# PicoUSBMotherboardV3_1.net
KiCad netlist of a schematic drawn in EasyEDA Pro
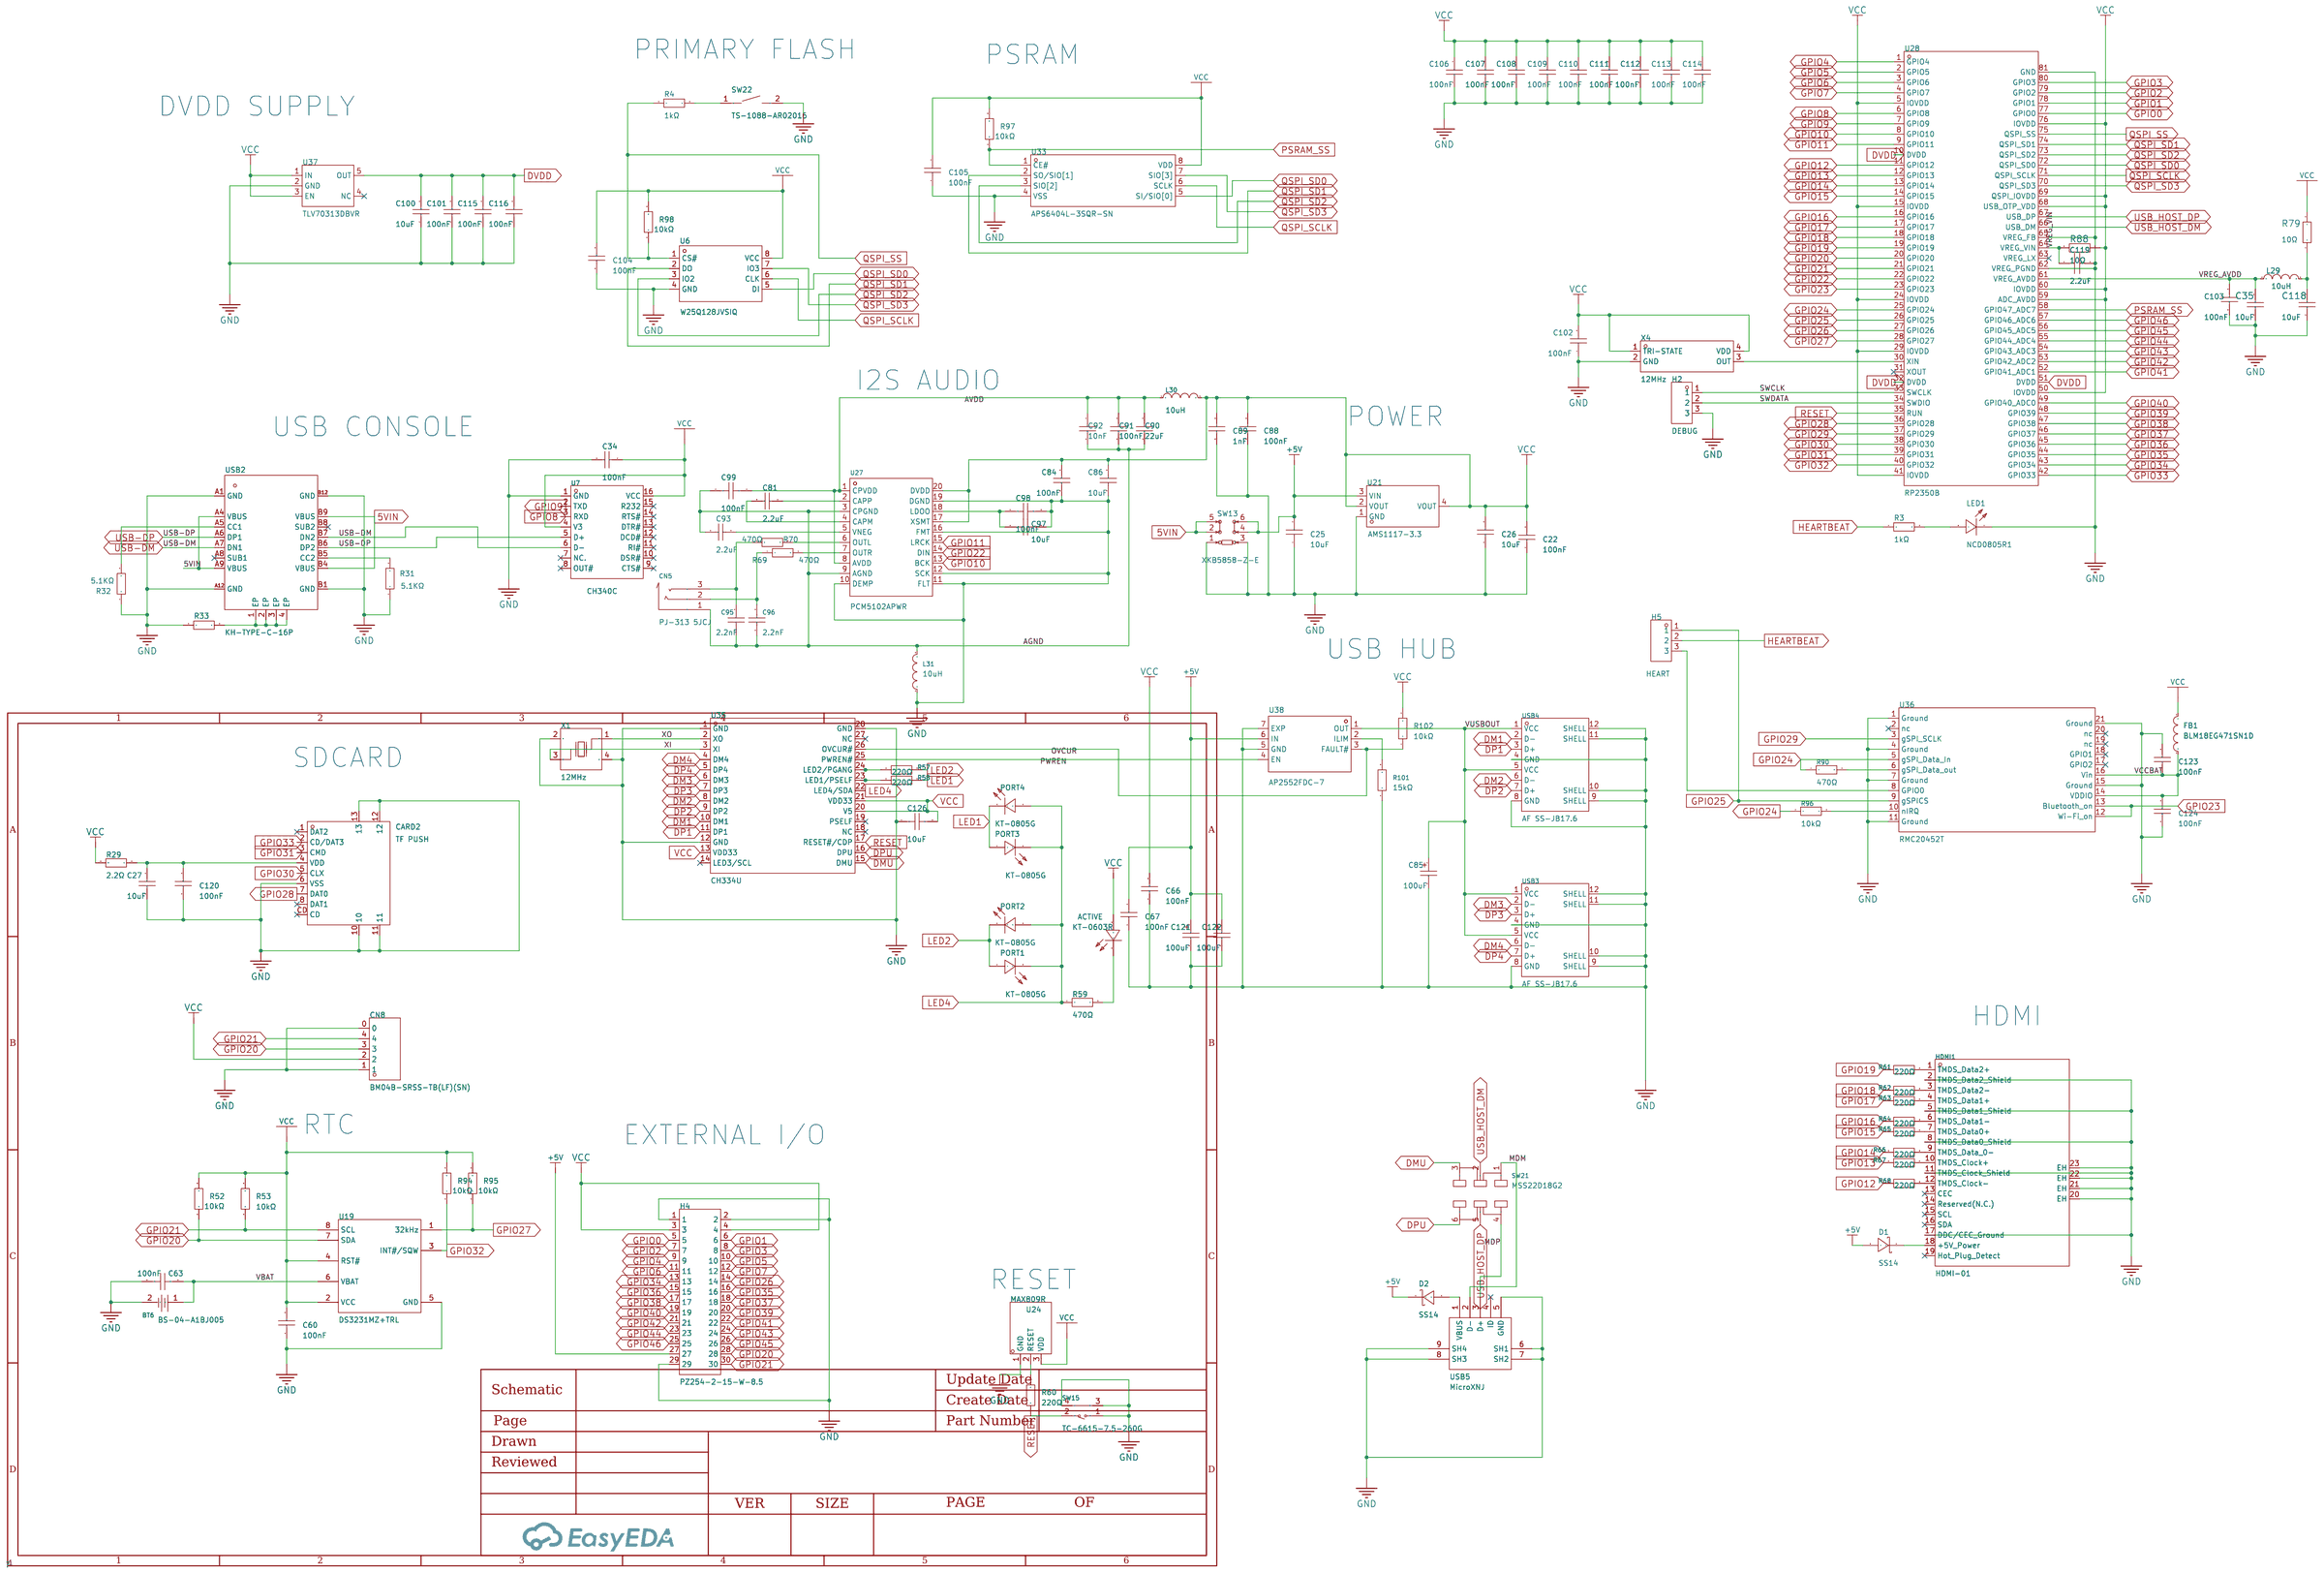
[diagram p0: schematic sheet]

(export (version "E")
  (design (tool "Eeschema 10.0.6"))
  (components
    (comp (ref "ACTIVE")
      (value "KT-0603R")
      (footprint "easyedapro:LED0603-RD")
      (fields (field (name "Manufacturer") "KENTO"))
      (libsource (lib "easyedapro") (part "KT-0603R"))
    )
    (comp (ref "BT6")
      (value "BS-04-A1BJ005")
      (footprint "easyedapro:BAT-TH_BS-04-A1BJ004")
      (fields (field (name "Manufacturer") "MYOUNG(美阳)"))
      (libsource (lib "easyedapro") (part "BS-04-A1BJ005"))
    )
    (comp (ref "C22")
      (value "100nF")
      (fields
        (field (name "Manufacturer Part") "CL05B104KO5NNNC")
        (field (name "Manufacturer") "SAMSUNG(三星)")
      )
      (libsource (lib "easyedapro") (part "cl10a225ko8nnnc"))
    )
    (comp (ref "C25")
      (value "10uF")
      (footprint "easyedapro:C1206")
      (fields
        (field (name "Manufacturer Part") "CL31A106KBHNNNE")
        (field (name "Manufacturer") "SAMSUNG(三星)")
      )
      (libsource (lib "easyedapro") (part "CL31A106KBHNNNE"))
    )
    (comp (ref "C26")
      (value "10uF")
      (footprint "easyedapro:C1206")
      (fields
        (field (name "Manufacturer Part") "CL31A106KBHNNNE")
        (field (name "Manufacturer") "SAMSUNG(三星)")
      )
      (libsource (lib "easyedapro") (part "CL31A106KBHNNNE"))
    )
    (comp (ref "C27")
      (value "10uF")
      (footprint "easyedapro:C1206")
      (fields
        (field (name "Manufacturer Part") "CL31A106KBHNNNE")
        (field (name "Manufacturer") "SAMSUNG(三星)")
      )
      (libsource (lib "easyedapro") (part "CL31A106KBHNNNE"))
    )
    (comp (ref "C34")
      (value "100nF")
      (fields
        (field (name "Manufacturer Part") "CL05B104KO5NNNC")
        (field (name "Manufacturer") "SAMSUNG(三星)")
      )
      (libsource (lib "easyedapro") (part "cl10a225ko8nnnc"))
    )
    (comp (ref "C35")
      (value "10uF")
      (footprint "easyedapro:C1206")
      (fields
        (field (name "Manufacturer Part") "CL31A106KBHNNNE")
        (field (name "Manufacturer") "SAMSUNG(三星)")
      )
      (libsource (lib "easyedapro") (part "CL31A106KBHNNNE"))
    )
    (comp (ref "C60")
      (value "100nF")
      (footprint "easyedapro:C0603")
      (fields
        (field (name "Manufacturer Part") "CL05B104KO5NNNC")
        (field (name "Manufacturer") "SAMSUNG(三星)")
      )
      (libsource (lib "easyedapro") (part "CL10A225KO8NNNC"))
    )
    (comp (ref "C63")
      (value "100nF")
      (footprint "easyedapro:C0402")
      (fields
        (field (name "Manufacturer Part") "CL05B104KB54PNC")
        (field (name "Manufacturer") "SAMSUNG(三星)")
      )
      (libsource (lib "easyedapro") (part "CL05B104KB54PNC"))
    )
    (comp (ref "C66")
      (value "100nF")
      (fields
        (field (name "Manufacturer Part") "CL05B104KO5NNNC")
        (field (name "Manufacturer") "SAMSUNG(三星)")
      )
      (libsource (lib "easyedapro") (part "cl10a225ko8nnnc"))
    )
    (comp (ref "C67")
      (value "100nF")
      (fields
        (field (name "Manufacturer Part") "CL05B104KO5NNNC")
        (field (name "Manufacturer") "SAMSUNG(三星)")
      )
      (libsource (lib "easyedapro") (part "cl10a225ko8nnnc"))
    )
    (comp (ref "C81")
      (value "2.2uF")
      (footprint "easyedapro:C0603")
      (fields
        (field (name "Manufacturer Part") "CL10A225KO8NNNC")
        (field (name "Manufacturer") "SAMSUNG(三星)")
      )
      (libsource (lib "easyedapro") (part "CL10A225KO8NNNC"))
    )
    (comp (ref "C84")
      (value "100nF")
      (fields
        (field (name "Manufacturer Part") "CL05B104KO5NNNC")
        (field (name "Manufacturer") "SAMSUNG(三星)")
      )
      (libsource (lib "easyedapro") (part "cl10a225ko8nnnc"))
    )
    (comp (ref "C85")
      (value "100uF")
      (footprint "easyedapro:CASE-B_3528")
      (fields (field (name "Manufacturer Part") "TAJB107K006RNJ") (field (name "Manufacturer") "Kyocera AVX"))
      (libsource (lib "easyedapro") (part "TAJB107K006RNJ"))
    )
    (comp (ref "C86")
      (value "10uF")
      (footprint "easyedapro:C1206")
      (fields
        (field (name "Manufacturer Part") "CL31A106KBHNNNE")
        (field (name "Manufacturer") "SAMSUNG(三星)")
      )
      (libsource (lib "easyedapro") (part "CL31A106KBHNNNE"))
    )
    (comp (ref "C88")
      (value "100nF")
      (fields
        (field (name "Manufacturer Part") "CL05B104KO5NNNC")
        (field (name "Manufacturer") "SAMSUNG(三星)")
      )
      (libsource (lib "easyedapro") (part "cl10a225ko8nnnc"))
    )
    (comp (ref "C89")
      (value "1nF")
      (footprint "easyedapro:C0805")
      (fields
        (field (name "Manufacturer Part") "CL21B102KBCNNNC")
        (field (name "Manufacturer") "SAMSUNG(三星)")
      )
      (libsource (lib "easyedapro") (part "CL21B102KBCNNNC"))
    )
    (comp (ref "C90")
      (value "22uF")
      (footprint "easyedapro:C1206")
      (fields
        (field (name "Manufacturer Part") "CL31A226KAHNNNE")
        (field (name "Manufacturer") "SAMSUNG(三星)")
      )
      (libsource (lib "easyedapro") (part "CL31A226KAHNNNE"))
    )
    (comp (ref "C91")
      (value "100nF")
      (fields
        (field (name "Manufacturer Part") "CL05B104KO5NNNC")
        (field (name "Manufacturer") "SAMSUNG(三星)")
      )
      (libsource (lib "easyedapro") (part "cl10a225ko8nnnc"))
    )
    (comp (ref "C92")
      (value "10nF")
      (footprint "easyedapro:C0805")
      (fields
        (field (name "Manufacturer Part") "CL21B103KBANNNC")
        (field (name "Manufacturer") "SAMSUNG(三星)")
      )
      (libsource (lib "easyedapro") (part "CL21B103KBANNNC"))
    )
    (comp (ref "C93")
      (value "2.2uF")
      (footprint "easyedapro:C0603")
      (fields
        (field (name "Manufacturer Part") "CL10A225KO8NNNC")
        (field (name "Manufacturer") "SAMSUNG(三星)")
      )
      (libsource (lib "easyedapro") (part "CL10A225KO8NNNC"))
    )
    (comp (ref "C95")
      (value "2.2nF")
      (footprint "easyedapro:C0805")
      (fields
        (field (name "Manufacturer Part") "CL21C222JBFNNNE")
        (field (name "Manufacturer") "SAMSUNG(三星)")
      )
      (libsource (lib "easyedapro") (part "CL21C222JBFNNNE"))
    )
    (comp (ref "C96")
      (value "2.2nF")
      (footprint "easyedapro:C0805")
      (fields
        (field (name "Manufacturer Part") "CL21C222JBFNNNE")
        (field (name "Manufacturer") "SAMSUNG(三星)")
      )
      (libsource (lib "easyedapro") (part "CL21C222JBFNNNE"))
    )
    (comp (ref "C97")
      (value "10uF")
      (footprint "easyedapro:C0805")
      (fields
        (field (name "Manufacturer Part") "CL21A106KAYNNNE")
        (field (name "Manufacturer") "SAMSUNG(三星)")
      )
      (libsource (lib "easyedapro") (part "CL21A106KAYNNNE"))
    )
    (comp (ref "C98")
      (value "100nF")
      (footprint "easyedapro:C0805")
      (fields
        (field (name "Manufacturer Part") "CC0805KRX7R9BB104")
        (field (name "Manufacturer") "YAGEO(国巨)")
      )
      (libsource (lib "easyedapro") (part "CC0805KRX7R9BB104"))
    )
    (comp (ref "C99")
      (value "100nF")
      (footprint "easyedapro:C0805")
      (fields
        (field (name "Manufacturer Part") "CC0805KRX7R9BB104")
        (field (name "Manufacturer") "YAGEO(国巨)")
      )
      (libsource (lib "easyedapro") (part "CC0805KRX7R9BB104"))
    )
    (comp (ref "C100")
      (value "10uF")
      (footprint "easyedapro:C1206")
      (fields
        (field (name "Manufacturer Part") "CL31A106KBHNNNE")
        (field (name "Manufacturer") "SAMSUNG(三星)")
      )
      (libsource (lib "easyedapro") (part "CL31A106KBHNNNE"))
    )
    (comp (ref "C101")
      (value "100nF")
      (fields
        (field (name "Manufacturer Part") "CL05B104KO5NNNC")
        (field (name "Manufacturer") "SAMSUNG(三星)")
      )
      (libsource (lib "easyedapro") (part "cl10a225ko8nnnc"))
    )
    (comp (ref "C102")
      (value "100nF")
      (fields
        (field (name "Manufacturer Part") "CL05B104KO5NNNC")
        (field (name "Manufacturer") "SAMSUNG(三星)")
      )
      (libsource (lib "easyedapro") (part "cl10a225ko8nnnc"))
    )
    (comp (ref "C103")
      (value "100nF")
      (fields
        (field (name "Manufacturer Part") "CL05B104KO5NNNC")
        (field (name "Manufacturer") "SAMSUNG(三星)")
      )
      (libsource (lib "easyedapro") (part "cl10a225ko8nnnc"))
    )
    (comp (ref "C104")
      (value "100nF")
      (footprint "easyedapro:C0805")
      (fields
        (field (name "Manufacturer Part") "CL21B104KCFNNNE")
        (field (name "Manufacturer") "SAMSUNG(三星)")
      )
      (libsource (lib "easyedapro") (part "CL21B104KCFNNNE"))
    )
    (comp (ref "C105")
      (value "100nF")
      (fields
        (field (name "Manufacturer Part") "CL05B104KO5NNNC")
        (field (name "Manufacturer") "SAMSUNG(三星)")
      )
      (libsource (lib "easyedapro") (part "cl10a225ko8nnnc"))
    )
    (comp (ref "C106")
      (value "100nF")
      (fields
        (field (name "Manufacturer Part") "CL05B104KO5NNNC")
        (field (name "Manufacturer") "SAMSUNG(三星)")
      )
      (libsource (lib "easyedapro") (part "cl10a225ko8nnnc"))
    )
    (comp (ref "C107")
      (value "100nF")
      (fields
        (field (name "Manufacturer Part") "CL05B104KO5NNNC")
        (field (name "Manufacturer") "SAMSUNG(三星)")
      )
      (libsource (lib "easyedapro") (part "cl10a225ko8nnnc"))
    )
    (comp (ref "C108")
      (value "100nF")
      (fields
        (field (name "Manufacturer Part") "CL05B104KO5NNNC")
        (field (name "Manufacturer") "SAMSUNG(三星)")
      )
      (libsource (lib "easyedapro") (part "cl10a225ko8nnnc"))
    )
    (comp (ref "C109")
      (value "100nF")
      (fields
        (field (name "Manufacturer Part") "CL05B104KO5NNNC")
        (field (name "Manufacturer") "SAMSUNG(三星)")
      )
      (libsource (lib "easyedapro") (part "cl10a225ko8nnnc"))
    )
    (comp (ref "C110")
      (value "100nF")
      (fields
        (field (name "Manufacturer Part") "CL05B104KO5NNNC")
        (field (name "Manufacturer") "SAMSUNG(三星)")
      )
      (libsource (lib "easyedapro") (part "cl10a225ko8nnnc"))
    )
    (comp (ref "C111")
      (value "100nF")
      (fields
        (field (name "Manufacturer Part") "CL05B104KO5NNNC")
        (field (name "Manufacturer") "SAMSUNG(三星)")
      )
      (libsource (lib "easyedapro") (part "cl10a225ko8nnnc"))
    )
    (comp (ref "C112")
      (value "100nF")
      (fields
        (field (name "Manufacturer Part") "CL05B104KO5NNNC")
        (field (name "Manufacturer") "SAMSUNG(三星)")
      )
      (libsource (lib "easyedapro") (part "cl10a225ko8nnnc"))
    )
    (comp (ref "C113")
      (value "100nF")
      (fields
        (field (name "Manufacturer Part") "CL05B104KO5NNNC")
        (field (name "Manufacturer") "SAMSUNG(三星)")
      )
      (libsource (lib "easyedapro") (part "cl10a225ko8nnnc"))
    )
    (comp (ref "C114")
      (value "100nF")
      (fields
        (field (name "Manufacturer Part") "CL05B104KO5NNNC")
        (field (name "Manufacturer") "SAMSUNG(三星)")
      )
      (libsource (lib "easyedapro") (part "cl10a225ko8nnnc"))
    )
    (comp (ref "C115")
      (value "100nF")
      (fields
        (field (name "Manufacturer Part") "CL05B104KO5NNNC")
        (field (name "Manufacturer") "SAMSUNG(三星)")
      )
      (libsource (lib "easyedapro") (part "cl10a225ko8nnnc"))
    )
    (comp (ref "C116")
      (value "100nF")
      (fields
        (field (name "Manufacturer Part") "CL05B104KO5NNNC")
        (field (name "Manufacturer") "SAMSUNG(三星)")
      )
      (libsource (lib "easyedapro") (part "cl10a225ko8nnnc"))
    )
    (comp (ref "C118")
      (value "10uF")
      (footprint "easyedapro:C1206")
      (fields
        (field (name "Manufacturer Part") "CL31A106KBHNNNE")
        (field (name "Manufacturer") "SAMSUNG(三星)")
      )
      (libsource (lib "easyedapro") (part "CL31A106KBHNNNE"))
    )
    (comp (ref "C119")
      (value "2.2uF")
      (footprint "easyedapro:C0402")
      (fields
        (field (name "Manufacturer Part") "CL05A225MQ5NSNC")
        (field (name "Manufacturer") "SAMSUNG(三星)")
      )
      (libsource (lib "easyedapro") (part "CL05A225MQ5NSNC"))
    )
    (comp (ref "C120")
      (value "100nF")
      (footprint "easyedapro:C0805")
      (fields
        (field (name "Manufacturer Part") "CL21B104KCFNNNE")
        (field (name "Manufacturer") "SAMSUNG(三星)")
      )
      (libsource (lib "easyedapro") (part "CL21B104KCFNNNE"))
    )
    (comp (ref "C121")
      (value "100uF")
      (footprint "easyedapro:CASE-B_3528")
      (fields (field (name "Manufacturer Part") "TAJB107K006RNJ") (field (name "Manufacturer") "Kyocera AVX"))
      (libsource (lib "easyedapro") (part "TAJB107K006RNJ"))
    )
    (comp (ref "C122")
      (value "100uF")
      (footprint "easyedapro:CASE-B_3528")
      (fields (field (name "Manufacturer Part") "TAJB107K006RNJ") (field (name "Manufacturer") "Kyocera AVX"))
      (libsource (lib "easyedapro") (part "TAJB107K006RNJ"))
    )
    (comp (ref "C123")
      (value "100nF")
      (fields
        (field (name "Manufacturer Part") "CL05B104KO5NNNC")
        (field (name "Manufacturer") "SAMSUNG(三星)")
      )
      (libsource (lib "easyedapro") (part "cl10a225ko8nnnc"))
    )
    (comp (ref "C124")
      (value "100nF")
      (fields
        (field (name "Manufacturer Part") "CL05B104KO5NNNC")
        (field (name "Manufacturer") "SAMSUNG(三星)")
      )
      (libsource (lib "easyedapro") (part "cl10a225ko8nnnc"))
    )
    (comp (ref "C126")
      (value "10uF")
      (footprint "easyedapro:C0603")
      (description "Capacitance:10uF Tolerance:±10% Tolerance:±10% Voltage Rating:10V Temperature Coefficient:X5R")
      (fields
        (field (name "Manufacturer Part") "CL10A106KP8NNNC")
        (field (name "Manufacturer") "SAMSUNG(三星)")
      )
      (libsource (lib "easyedapro") (part "CL10A106KP8NNNC"))
    )
    (comp (ref "CARD2")
      (value "TF PUSH")
      (footprint "easyedapro:TF-SMD_TF-PUSH")
      (fields (field (name "Manufacturer") "SHOU HAN(首韩)"))
      (libsource (lib "easyedapro") (part "TF PUSH"))
    )
    (comp (ref "CN5")
      (value "PJ-313 5JCJ")
      (footprint "easyedapro:AUDIO-TH_PJ-313_5JCJ")
      (fields (field (name "Manufacturer") "SHOU HAN(首韩)"))
      (libsource (lib "easyedapro") (part "PJ-313 5JCJ"))
    )
    (comp (ref "CN8")
      (value "BM04B-SRSS-TB(LF)(SN)")
      (footprint "easyedapro:CONN-SMD_BM04B-SRSS-TB")
      (fields (field (name "Manufacturer") "JST"))
      (libsource (lib "easyedapro") (part "BM04B-SRSS-TB(LF)(SN)"))
    )
    (comp (ref "D1")
      (value "SS14")
      (footprint "easyedapro:SMA_L4.2-W2.6-LS5.3-RD")
      (fields (field (name "Manufacturer") "MDD(辰达半导体)"))
      (libsource (lib "easyedapro") (part "SS14"))
    )
    (comp (ref "D2")
      (value "SS14")
      (footprint "easyedapro:SMA_L4.2-W2.6-LS5.3-RD")
      (fields (field (name "Manufacturer") "MDD(辰达半导体)"))
      (libsource (lib "easyedapro") (part "SS14"))
    )
    (comp (ref "FB1")
      (value "BLM18EG471SN1D")
      (footprint "easyedapro:L0603")
      (fields (field (name "Manufacturer") "muRata(村田)"))
      (libsource (lib "easyedapro") (part "BLM18EG471SN1D"))
    )
    (comp (ref "H2")
      (value "DEBUG")
      (footprint "easyedapro:HDR-TH_3P-P2.54-V-M")
      (fields (field (name "Manufacturer Part") "PZ254V-11-03P") (field (name "Manufacturer") "XFCN(兴飞)"))
      (libsource (lib "easyedapro") (part "PZ254V-11-03P_C2937625"))
    )
    (comp (ref "H4")
      (value "PZ254-2-15-W-8.5")
      (footprint "easyedapro:HDR-TH_30P-P2.54-H-M-R2-C15-S2.54-N")
      (fields (field (name "Manufacturer") "HCTL(华灿天禄)"))
      (libsource (lib "easyedapro") (part "PZ254-2-15-W-8.5"))
    )
    (comp (ref "H5")
      (value "HEART")
      (footprint "easyedapro:HDR-TH_3P-P2.54-V-M")
      (fields (field (name "Manufacturer Part") "PZ254V-11-03P") (field (name "Manufacturer") "XFCN(兴飞)"))
      (libsource (lib "easyedapro") (part "PZ254V-11-03P_C2937625"))
    )
    (comp (ref "HDMI1")
      (value "HDMI-01")
      (footprint "easyedapro:USB-SMD_HDMI-01")
      (fields (field (name "Manufacturer") "HCTL(华灿天禄)"))
      (libsource (lib "easyedapro") (part "HDMI-01"))
    )
    (comp (ref "L29")
      (value "10uH")
      (fields
        (field (name "Manufacturer Part") "SDFL2012S100KTF")
        (field (name "Manufacturer") "Sunlord(顺络)")
      )
      (libsource (lib "easyedapro") (part "SDFL2012S100KTF"))
    )
    (comp (ref "L30")
      (value "10uH")
      (footprint "easyedapro:L0805")
      (fields (field (name "Manufacturer Part") "MLZ2012M100HT000") (field (name "Manufacturer") "TDK"))
      (libsource (lib "easyedapro") (part "MLZ2012M100HT000"))
    )
    (comp (ref "L31")
      (value "10uH")
      (footprint "easyedapro:L0805")
      (fields (field (name "Manufacturer Part") "MLZ2012M100HT000") (field (name "Manufacturer") "TDK"))
      (libsource (lib "easyedapro") (part "MLZ2012M100HT000"))
    )
    (comp (ref "LED1")
      (value "NCD0805R1")
      (footprint "easyedapro:LED0805-RD")
      (description "Emitted Color:红灯")
      (fields (field (name "Manufacturer") "国星光电"))
      (libsource (lib "easyedapro") (part "FC-2012HRK-620D"))
    )
    (comp (ref "PORT1")
      (value "KT-0805G")
      (footprint "easyedapro:LED0805-R-RD")
      (fields (field (name "Manufacturer") "KENTO"))
      (libsource (lib "easyedapro") (part "0805G (Green)"))
    )
    (comp (ref "PORT2")
      (value "KT-0805G")
      (footprint "easyedapro:LED0805-R-RD")
      (fields (field (name "Manufacturer") "KENTO"))
      (libsource (lib "easyedapro") (part "0805G (Green)"))
    )
    (comp (ref "PORT3")
      (value "KT-0805G")
      (footprint "easyedapro:LED0805-R-RD")
      (fields (field (name "Manufacturer") "KENTO"))
      (libsource (lib "easyedapro") (part "0805G (Green)"))
    )
    (comp (ref "PORT4")
      (value "KT-0805G")
      (footprint "easyedapro:LED0805-R-RD")
      (fields (field (name "Manufacturer") "KENTO"))
      (libsource (lib "easyedapro") (part "0805G (Green)"))
    )
    (comp (ref "R3")
      (value "1kΩ")
      (footprint "easyedapro:R0603")
      (fields
        (field (name "Manufacturer Part") "0603WAF1001T5E")
        (field (name "Manufacturer") "UNI-ROYAL(厚声)")
      )
      (libsource (lib "easyedapro") (part "0603WAF1001T5E"))
    )
    (comp (ref "R4")
      (value "1kΩ")
      (footprint "easyedapro:R0603")
      (fields
        (field (name "Manufacturer Part") "0603WAF1001T5E")
        (field (name "Manufacturer") "UNI-ROYAL(厚声)")
      )
      (libsource (lib "easyedapro") (part "0603WAF1001T5E"))
    )
    (comp (ref "R29")
      (value "2.2Ω")
      (footprint "easyedapro:R0805")
      (fields (field (name "Manufacturer") "UNI-ROYAL(厚声)"))
      (libsource (lib "easyedapro") (part "0805W8F220KT5E"))
    )
    (comp (ref "R31")
      (value "5.1kΩ")
      (fields
        (field (name "Manufacturer Part") "5.1KΩ")
        (field (name "Manufacturer") "UNI-ROYAL(厚声)")
        (field (name "Tolerance") "±1%")
      )
      (libsource (lib "easyedapro") (part "0603waf5101t5e"))
    )
    (comp (ref "R32")
      (value "5.1kΩ")
      (fields
        (field (name "Manufacturer Part") "5.1KΩ")
        (field (name "Manufacturer") "UNI-ROYAL(厚声)")
        (field (name "Tolerance") "±1%")
      )
      (libsource (lib "easyedapro") (part "0603waf5101t5e"))
    )
    (comp (ref "R33")
      (value "1MΩ")
      (fields
        (field (name "Manufacturer Part") "0402WGF1004TCE")
        (field (name "Manufacturer") "UNI-ROYAL(厚声)")
      )
      (libsource (lib "easyedapro") (part "0603waf1004t5e"))
    )
    (comp (ref "R52")
      (value "10kΩ")
      (footprint "easyedapro:R0805")
      (fields
        (field (name "Manufacturer Part") "0805W8F1002T5E")
        (field (name "Manufacturer") "UNI-ROYAL(厚声)")
      )
      (libsource (lib "easyedapro") (part "0805W8F1002T5E"))
    )
    (comp (ref "R53")
      (value "10kΩ")
      (footprint "easyedapro:R0805")
      (fields
        (field (name "Manufacturer Part") "0805W8F1002T5E")
        (field (name "Manufacturer") "UNI-ROYAL(厚声)")
      )
      (libsource (lib "easyedapro") (part "0805W8F1002T5E"))
    )
    (comp (ref "R57")
      (value "220Ω")
      (footprint "easyedapro:R0805")
      (fields
        (field (name "Manufacturer Part") "0805W8F2200T5E")
        (field (name "Manufacturer") "UNI-ROYAL(厚声)")
      )
      (libsource (lib "easyedapro") (part "0805W8F2200T5E"))
    )
    (comp (ref "R58")
      (value "220Ω")
      (footprint "easyedapro:R0805")
      (fields
        (field (name "Manufacturer Part") "0805W8F2200T5E")
        (field (name "Manufacturer") "UNI-ROYAL(厚声)")
      )
      (libsource (lib "easyedapro") (part "0805W8F2200T5E"))
    )
    (comp (ref "R59")
      (value "470Ω")
      (footprint "easyedapro:R0603")
      (fields
        (field (name "Manufacturer Part") "0603WAF4700T5E")
        (field (name "Manufacturer") "UNI-ROYAL(厚声)")
      )
      (libsource (lib "easyedapro") (part "0603WAF4700T5E"))
    )
    (comp (ref "R60")
      (value "220Ω")
      (footprint "easyedapro:R0603")
      (fields
        (field (name "Manufacturer Part") "0603WAF2200T5E")
        (field (name "Manufacturer") "UNI-ROYAL(厚声)")
      )
      (libsource (lib "easyedapro") (part "0603WAF2200T5E"))
    )
    (comp (ref "R61")
      (value "220Ω")
      (footprint "easyedapro:R0603")
      (fields
        (field (name "Manufacturer Part") "0603WAF2200T5E")
        (field (name "Manufacturer") "UNI-ROYAL(厚声)")
      )
      (libsource (lib "easyedapro") (part "0603WAF2200T5E"))
    )
    (comp (ref "R62")
      (value "220Ω")
      (footprint "easyedapro:R0603")
      (fields
        (field (name "Manufacturer Part") "0603WAF2200T5E")
        (field (name "Manufacturer") "UNI-ROYAL(厚声)")
      )
      (libsource (lib "easyedapro") (part "0603WAF2200T5E"))
    )
    (comp (ref "R63")
      (value "220Ω")
      (footprint "easyedapro:R0603")
      (fields
        (field (name "Manufacturer Part") "0603WAF2200T5E")
        (field (name "Manufacturer") "UNI-ROYAL(厚声)")
      )
      (libsource (lib "easyedapro") (part "0603WAF2200T5E"))
    )
    (comp (ref "R64")
      (value "220Ω")
      (footprint "easyedapro:R0603")
      (fields
        (field (name "Manufacturer Part") "0603WAF2200T5E")
        (field (name "Manufacturer") "UNI-ROYAL(厚声)")
      )
      (libsource (lib "easyedapro") (part "0603WAF2200T5E"))
    )
    (comp (ref "R65")
      (value "220Ω")
      (footprint "easyedapro:R0603")
      (fields
        (field (name "Manufacturer Part") "0603WAF2200T5E")
        (field (name "Manufacturer") "UNI-ROYAL(厚声)")
      )
      (libsource (lib "easyedapro") (part "0603WAF2200T5E"))
    )
    (comp (ref "R66")
      (value "220Ω")
      (footprint "easyedapro:R0603")
      (fields
        (field (name "Manufacturer Part") "0603WAF2200T5E")
        (field (name "Manufacturer") "UNI-ROYAL(厚声)")
      )
      (libsource (lib "easyedapro") (part "0603WAF2200T5E"))
    )
    (comp (ref "R67")
      (value "220Ω")
      (footprint "easyedapro:R0603")
      (fields
        (field (name "Manufacturer Part") "0603WAF2200T5E")
        (field (name "Manufacturer") "UNI-ROYAL(厚声)")
      )
      (libsource (lib "easyedapro") (part "0603WAF2200T5E"))
    )
    (comp (ref "R68")
      (value "220Ω")
      (footprint "easyedapro:R0603")
      (fields
        (field (name "Manufacturer Part") "0603WAF2200T5E")
        (field (name "Manufacturer") "UNI-ROYAL(厚声)")
      )
      (libsource (lib "easyedapro") (part "0603WAF2200T5E"))
    )
    (comp (ref "R69")
      (value "470Ω")
      (footprint "easyedapro:R0603")
      (fields
        (field (name "Manufacturer Part") "0603WAF4700T5E")
        (field (name "Manufacturer") "UNI-ROYAL(厚声)")
      )
      (libsource (lib "easyedapro") (part "0603WAF4700T5E"))
    )
    (comp (ref "R70")
      (value "470Ω")
      (footprint "easyedapro:R0603")
      (fields
        (field (name "Manufacturer Part") "0603WAF4700T5E")
        (field (name "Manufacturer") "UNI-ROYAL(厚声)")
      )
      (libsource (lib "easyedapro") (part "0603WAF4700T5E"))
    )
    (comp (ref "R79")
      (value "10Ω")
      (footprint "easyedapro:R0805_NEW")
      (fields
        (field (name "Manufacturer Part") "0805W8F100JT5E")
        (field (name "Manufacturer") "UNI-ROYAL(厚声)")
      )
      (libsource (lib "easyedapro") (part "0805W8F100JT5E"))
    )
    (comp (ref "R88")
      (value "10Ω")
      (footprint "easyedapro:R0805_NEW")
      (fields
        (field (name "Manufacturer Part") "0805W8F100JT5E")
        (field (name "Manufacturer") "UNI-ROYAL(厚声)")
      )
      (libsource (lib "easyedapro") (part "0805W8F100JT5E"))
    )
    (comp (ref "R90")
      (value "470Ω")
      (footprint "easyedapro:R0402")
      (fields
        (field (name "Manufacturer Part") "0402WGF4700TCE")
        (field (name "Manufacturer") "UNI-ROYAL(厚声)")
      )
      (libsource (lib "easyedapro") (part "0402WGF4700TCE"))
    )
    (comp (ref "R94")
      (value "10kΩ")
      (footprint "easyedapro:R0805")
      (fields
        (field (name "Manufacturer Part") "0805W8F1002T5E")
        (field (name "Manufacturer") "UNI-ROYAL(厚声)")
      )
      (libsource (lib "easyedapro") (part "0805W8F1002T5E"))
    )
    (comp (ref "R95")
      (value "10kΩ")
      (footprint "easyedapro:R0805")
      (fields
        (field (name "Manufacturer Part") "0805W8F1002T5E")
        (field (name "Manufacturer") "UNI-ROYAL(厚声)")
      )
      (libsource (lib "easyedapro") (part "0805W8F1002T5E"))
    )
    (comp (ref "R96")
      (value "10kΩ")
      (footprint "easyedapro:R0603")
      (fields
        (field (name "Manufacturer Part") "0603WAF1002T5E")
        (field (name "Manufacturer") "UNI-ROYAL(厚声)")
      )
      (libsource (lib "easyedapro") (part "0603WAF1002T5E"))
    )
    (comp (ref "R97")
      (value "10kΩ")
      (footprint "easyedapro:R0805")
      (fields
        (field (name "Manufacturer Part") "0805W8F1002T5E")
        (field (name "Manufacturer") "UNI-ROYAL(厚声)")
      )
      (libsource (lib "easyedapro") (part "0805W8F1002T5E"))
    )
    (comp (ref "R98")
      (value "10kΩ")
      (footprint "easyedapro:R0805")
      (fields
        (field (name "Manufacturer Part") "0805W8F1002T5E")
        (field (name "Manufacturer") "UNI-ROYAL(厚声)")
      )
      (libsource (lib "easyedapro") (part "0805W8F1002T5E"))
    )
    (comp (ref "R101")
      (value "15kΩ")
      (footprint "easyedapro:R0402")
      (fields
        (field (name "Manufacturer Part") "0402WGF1502TCE")
        (field (name "Manufacturer") "UNI-ROYAL(厚声)")
      )
      (libsource (lib "easyedapro") (part "0402WGF1502TCE"))
    )
    (comp (ref "R102")
      (value "10kΩ")
      (footprint "easyedapro:R0805")
      (fields
        (field (name "Manufacturer Part") "0805W8F1002T5E")
        (field (name "Manufacturer") "UNI-ROYAL(厚声)")
      )
      (libsource (lib "easyedapro") (part "0805W8F1002T5E"))
    )
    (comp (ref "SW13")
      (value "XKB5858-Z-E")
      (footprint "easyedapro:SW-TH_XKB5858-Z-E")
      (fields (field (name "Manufacturer") "XKB Connectivity(中国星坤)"))
      (libsource (lib "easyedapro") (part "XKB5858-Z-E"))
    )
    (comp (ref "SW15")
      (value "TC-6615-7.5-260G")
      (footprint "easyedapro:SW-TH_4P-L7.5-W7.5-P4.50")
      (fields (field (name "Manufacturer") "HCTL(华灿天禄)"))
      (libsource (lib "easyedapro") (part "TC-6615-7.5-260G"))
    )
    (comp (ref "SW21")
      (value "MSS22D18G2")
      (footprint "easyedapro:SW-TH_MSS22D18GX")
      (fields (field (name "Manufacturer") "SHOU HAN(首韩)"))
      (libsource (lib "easyedapro") (part "MSS22D18G2"))
    )
    (comp (ref "SW22")
      (value "TS-1088-AR02016")
      (footprint "easyedapro:SW-SMD_L3.9-W3.0-P4.45")
      (fields (field (name "Manufacturer") "XUNPU(讯普)"))
      (libsource (lib "easyedapro") (part "TS-1088-AR02016"))
    )
    (comp (ref "U6")
      (value "W25Q128JVSIQ")
      (footprint "easyedapro:SOIC-8_L5.3-W5.3-P1.27-LS8.0-BL")
      (fields (field (name "Manufacturer") "WINBOND(华邦)"))
      (libsource (lib "easyedapro") (part "W25Q128JVSIQTR"))
    )
    (comp (ref "U7")
      (value "CH340C")
      (footprint "easyedapro:SOP-16_L10.0-W3.9-P1.27-LS6.0-BL")
      (fields (field (name "Manufacturer") "WCH(南京沁恒)"))
      (libsource (lib "easyedapro") (part "CH340C"))
    )
    (comp (ref "U19")
      (value "DS3231MZ+TRL")
      (footprint "easyedapro:SOIC-8_L4.9-W3.9-P1.27-LS6.0-BL")
      (fields (field (name "Manufacturer") "ADI(亚德诺)/MAXIM(美信)"))
      (libsource (lib "easyedapro") (part "DS3231MZ+"))
    )
    (comp (ref "U21")
      (value "AMS1117-3.3")
      (footprint "easyedapro:SOT-223-3_L6.5-W3.4-P2.30-LS7.0-BR")
      (fields (field (name "Manufacturer") "AMS"))
      (libsource (lib "easyedapro") (part "AMS1117-3.3"))
    )
    (comp (ref "U24")
      (value "MAX809R")
      (footprint "easyedapro:SOT-23-3_L2.9-W1.3-P1.90-LS2.4-BR")
      (fields (field (name "Manufacturer") "UMW(友台半导体)"))
      (libsource (lib "easyedapro") (part "MAX809R"))
    )
    (comp (ref "U27")
      (value "PCM5102APWR")
      (footprint "easyedapro:TSSOP-20_L6.5-W4.4-P0.65-LS6.4-BL")
      (fields (field (name "Manufacturer") "TI(德州仪器)"))
      (libsource (lib "easyedapro") (part "PCM5102APWR"))
    )
    (comp (ref "U28")
      (value "RP2350B")
      (footprint "easyedapro:QFN-80_L10.0-W10.0-P0.40-TL-EP3.4")
      (fields (field (name "Manufacturer") "Raspberry Pi(树莓派)"))
      (libsource (lib "easyedapro") (part "RP2350B_C42415655"))
    )
    (comp (ref "U33")
      (value "APS6404L-3SQR-SN")
      (footprint "easyedapro:SOIC-8_L4.9-W3.9-P1.27-LS6.0-BL")
      (fields (field (name "Manufacturer") "Apmemory"))
      (libsource (lib "easyedapro") (part "APS6404L-3SQR-SN_C5333729"))
    )
    (comp (ref "U35")
      (value "CH334U")
      (footprint "easyedapro:QSOP-28_L9.9-W3.9-P0.64-LS6.0-BL")
      (fields (field (name "Manufacturer") "WCH(南京沁恒)"))
      (libsource (lib "easyedapro") (part "CH334U"))
    )
    (comp (ref "U36")
      (value "RMC20452T")
      (footprint "easyedapro:WIRELM-SMD_RMC20452T")
      (fields (field (name "Manufacturer") "Raspberry Pi(树莓派)"))
      (libsource (lib "easyedapro") (part "RMC20452T_C49451547"))
    )
    (comp (ref "U37")
      (value "TLV70313DBVR")
      (footprint "easyedapro:SOT-23-5_L3.0-W1.5-P0.95-LS2.8-BL")
      (fields (field (name "Manufacturer") "TI(德州仪器)"))
      (libsource (lib "easyedapro") (part "TLV70313DBVR"))
    )
    (comp (ref "U38")
      (value "AP2552FDC-7")
      (footprint "easyedapro:WDFN-6_L2.0-W2.0-P0.65-BL-EP-1")
      (fields (field (name "Manufacturer") "DIODES(美台)"))
      (libsource (lib "easyedapro") (part "AP2552FDC-7"))
    )
    (comp (ref "USB2")
      (value "KH-TYPE-C-16P")
      (footprint "easyedapro:USB-C-SMD_KH-TYPE-C-16P")
      (fields (field (name "Manufacturer") "kinghelm(金航标)"))
      (libsource (lib "easyedapro") (part "KH-TYPE-C-16P"))
    )
    (comp (ref "USB3")
      (value "AF SS-JB17.6")
      (footprint "easyedapro:USB-A-TH_AF-SS-JB17.6")
      (fields (field (name "Manufacturer") "SHOU HAN(首韩)"))
      (libsource (lib "easyedapro") (part "AF SS-JB17.6"))
    )
    (comp (ref "USB4")
      (value "AF SS-JB17.6")
      (footprint "easyedapro:USB-A-TH_AF-SS-JB17.6")
      (fields (field (name "Manufacturer") "SHOU HAN(首韩)"))
      (libsource (lib "easyedapro") (part "AF SS-JB17.6"))
    )
    (comp (ref "USB5")
      (value "MicroXNJ")
      (footprint "easyedapro:MICRO-USB-SMD_MICROXNJ")
      (fields (field (name "Manufacturer") "SHOU HAN(首韩)"))
      (libsource (lib "easyedapro") (part "MICROXNJ"))
    )
    (comp (ref "X1")
      (value "12MHz")
      (footprint "easyedapro:OSC-SMD_4P-L3.2-W2.5-BL")
      (fields (field (name "Manufacturer Part") "X322512MSB4SI") (field (name "Manufacturer") "YXC(扬兴晶振)"))
      (libsource (lib "easyedapro") (part "X322512MSB4SI"))
    )
    (comp (ref "X4")
      (value "12MHz")
      (footprint "easyedapro:OSC-SMD_4P-L3.2-W2.5-BL")
      (fields (field (name "Manufacturer Part") "XOS32012000LT00351005") (field (name "Manufacturer") "同晶"))
      (libsource (lib "easyedapro") (part "XOS32012000LT00351005"))
    )
  )
  (nets
    (net (code "1") (name "+5V") (class "Default")
      (node (ref "C121") (pin "1") (pinfunction "1_1") (pintype "input"))
      (node (ref "C122") (pin "1") (pinfunction "1_1") (pintype "input"))
      (node (ref "C25") (pin "2") (pinfunction "2_2") (pintype "input"))
      (node (ref "C67") (pin "2") (pinfunction "2_2") (pintype "input"))
      (node (ref "D1") (pin "2") (pinfunction "A_2") (pintype "unspecified"))
      (node (ref "D2") (pin "1") (pinfunction "K_1") (pintype "unspecified"))
      (node (ref "H4") (pin "27") (pinfunction "27_27") (pintype "unspecified"))
      (node (ref "SW13") (pin "4") (pinfunction "4_4") (pintype "input"))
      (node (ref "SW13") (pin "6") (pinfunction "6_6") (pintype "input"))
      (node (ref "U21") (pin "3") (pinfunction "VIN_3") (pintype "input"))
      (node (ref "U38") (pin "6") (pinfunction "IN_6") (pintype "unspecified"))
    )
    (net (code "2") (name "/AGND") (class "Default")
      (node (ref "C90") (pin "1") (pinfunction "1_1") (pintype "input"))
      (node (ref "C91") (pin "1") (pinfunction "1_1") (pintype "input"))
      (node (ref "C92") (pin "1") (pinfunction "1_1") (pintype "input"))
      (node (ref "C93") (pin "2") (pinfunction "2_2") (pintype "input"))
      (node (ref "C95") (pin "1") (pinfunction "1_1") (pintype "input"))
      (node (ref "C96") (pin "1") (pinfunction "1_1") (pintype "input"))
      (node (ref "C99") (pin "1") (pinfunction "1_1") (pintype "unspecified"))
      (node (ref "CN5") (pin "1") (pinfunction "1_1") (pintype "input"))
      (node (ref "L31") (pin "2") (pinfunction "2_2") (pintype "input"))
      (node (ref "U27") (pin "3") (pinfunction "CPGND_3") (pintype "input"))
      (node (ref "U27") (pin "9") (pinfunction "AGND_9") (pintype "input"))
    )
    (net (code "3") (name "/AVDD") (class "Default")
      (node (ref "C90") (pin "2") (pinfunction "2_2") (pintype "input"))
      (node (ref "C91") (pin "2") (pinfunction "2_2") (pintype "input"))
      (node (ref "C92") (pin "2") (pinfunction "2_2") (pintype "input"))
      (node (ref "C99") (pin "2") (pinfunction "2_2") (pintype "unspecified"))
      (node (ref "L30") (pin "1") (pinfunction "1_1") (pintype "input"))
      (node (ref "U27") (pin "1") (pinfunction "CPVDD_1") (pintype "input"))
      (node (ref "U27") (pin "8") (pinfunction "AVDD_8") (pintype "input"))
    )
    (net (code "4") (name "/MDM") (class "Default")
      (node (ref "SW21") (pin "1") (pinfunction "1_1") (pintype "input"))
      (node (ref "USB5") (pin "2") (pinfunction "D-_2") (pintype "unspecified"))
    )
    (net (code "5") (name "/MDP") (class "Default")
      (node (ref "SW21") (pin "4") (pinfunction "4_4") (pintype "input"))
      (node (ref "USB5") (pin "3") (pinfunction "D+_3") (pintype "unspecified"))
    )
    (net (code "6") (name "/OVCUR") (class "Default")
      (node (ref "R102") (pin "1") (pinfunction "1_1") (pintype "input"))
      (node (ref "U35") (pin "26") (pinfunction "OVCUR#_26") (pintype "unspecified"))
      (node (ref "U38") (pin "3") (pinfunction "FAULT#_3") (pintype "unspecified"))
    )
    (net (code "7") (name "/PWREN") (class "Default")
      (node (ref "U35") (pin "25") (pinfunction "PWREN#_25") (pintype "unspecified"))
      (node (ref "U38") (pin "4") (pinfunction "EN_4") (pintype "unspecified"))
    )
    (net (code "8") (name "/SWCLK") (class "Default")
      (node (ref "H2") (pin "1") (pinfunction "1_1") (pintype "unspecified"))
      (node (ref "U28") (pin "33") (pinfunction "SWCLK_33") (pintype "unspecified"))
    )
    (net (code "9") (name "/SWDATA") (class "Default")
      (node (ref "H2") (pin "2") (pinfunction "2_2") (pintype "unspecified"))
      (node (ref "U28") (pin "34") (pinfunction "SWDIO_34") (pintype "unspecified"))
    )
    (net (code "10") (name "/VBAT") (class "Default")
      (node (ref "BT6") (pin "1") (pinfunction "1_1") (pintype "input"))
      (node (ref "C63") (pin "1") (pinfunction "1_1") (pintype "input"))
      (node (ref "U19") (pin "6") (pinfunction "VBAT_6") (pintype "unspecified"))
    )
    (net (code "11") (name "/VCCBAT") (class "Default")
      (node (ref "C123") (pin "1") (pinfunction "1_1") (pintype "input"))
      (node (ref "C124") (pin "2") (pinfunction "2_2") (pintype "input"))
      (node (ref "FB1") (pin "1") (pinfunction "1_1") (pintype "unspecified"))
      (node (ref "U36") (pin "14") (pinfunction "VDDIO_14") (pintype "unspecified"))
      (node (ref "U36") (pin "16") (pinfunction "Vin_16") (pintype "unspecified"))
    )
    (net (code "12") (name "/VREG_AVDD") (class "Default")
      (node (ref "C103") (pin "2") (pinfunction "2_2") (pintype "input"))
      (node (ref "C35") (pin "2") (pinfunction "2_2") (pintype "input"))
      (node (ref "L29") (pin "1") (pinfunction "1_1") (pintype "unspecified"))
      (node (ref "U28") (pin "61") (pinfunction "VREG_AVDD_61") (pintype "unspecified"))
    )
    (net (code "13") (name "/VREG_VIN") (class "Default")
      (node (ref "C119") (pin "1") (pinfunction "1_1") (pintype "unspecified"))
      (node (ref "R88") (pin "2") (pinfunction "2_2") (pintype "input"))
      (node (ref "U28") (pin "64") (pinfunction "VREG_VIN_64") (pintype "unspecified"))
    )
    (net (code "14") (name "/VUSBOUT") (class "Default")
      (node (ref "C85") (pin "1") (pinfunction "1_1") (pintype "input"))
      (node (ref "U38") (pin "1") (pinfunction "OUT_1") (pintype "unspecified"))
      (node (ref "USB3") (pin "1") (pinfunction "VCC_1") (pintype "input"))
      (node (ref "USB3") (pin "5") (pinfunction "VCC_5") (pintype "input"))
      (node (ref "USB4") (pin "1") (pinfunction "VCC_1") (pintype "input"))
      (node (ref "USB4") (pin "5") (pinfunction "VCC_5") (pintype "input"))
    )
    (net (code "15") (name "/XI") (class "Default")
      (node (ref "U35") (pin "3") (pinfunction "XI_3") (pintype "unspecified"))
      (node (ref "X1") (pin "3") (pinfunction "OSC2_3") (pintype "unspecified"))
    )
    (net (code "16") (name "/XO") (class "Default")
      (node (ref "U35") (pin "2") (pinfunction "XO_2") (pintype "unspecified"))
      (node (ref "X1") (pin "1") (pinfunction "OSC1_1") (pintype "unspecified"))
    )
    (net (code "17") (name "5VIN") (class "Default")
      (node (ref "SW13") (pin "2") (pinfunction "2_2") (pintype "input"))
      (node (ref "SW13") (pin "5") (pinfunction "5_5") (pintype "input"))
      (node (ref "USB2") (pin "A4") (pinfunction "VBUS_A4") (pintype "input"))
      (node (ref "USB2") (pin "A9") (pinfunction "VBUS_A9") (pintype "input"))
      (node (ref "USB2") (pin "B4") (pinfunction "VBUS_B4") (pintype "input"))
      (node (ref "USB2") (pin "B9") (pinfunction "VBUS_B9") (pintype "input"))
    )
    (net (code "18") (name "DM1") (class "Default")
      (node (ref "U35") (pin "10") (pinfunction "DM1_10") (pintype "unspecified"))
      (node (ref "USB4") (pin "2") (pinfunction "D-_2") (pintype "input"))
    )
    (net (code "19") (name "DM2") (class "Default")
      (node (ref "U35") (pin "8") (pinfunction "DM2_8") (pintype "unspecified"))
      (node (ref "USB4") (pin "6") (pinfunction "D-_6") (pintype "input"))
    )
    (net (code "20") (name "DM3") (class "Default")
      (node (ref "U35") (pin "6") (pinfunction "DM3_6") (pintype "unspecified"))
      (node (ref "USB3") (pin "2") (pinfunction "D-_2") (pintype "input"))
    )
    (net (code "21") (name "DM4") (class "Default")
      (node (ref "U35") (pin "4") (pinfunction "DM4_4") (pintype "unspecified"))
      (node (ref "USB3") (pin "6") (pinfunction "D-_6") (pintype "input"))
    )
    (net (code "22") (name "DMU") (class "Default")
      (node (ref "SW21") (pin "3") (pinfunction "3_3") (pintype "input"))
      (node (ref "U35") (pin "15") (pinfunction "DMU_15") (pintype "unspecified"))
    )
    (net (code "23") (name "DP1") (class "Default")
      (node (ref "U35") (pin "11") (pinfunction "DP1_11") (pintype "unspecified"))
      (node (ref "USB4") (pin "3") (pinfunction "D+_3") (pintype "input"))
    )
    (net (code "24") (name "DP2") (class "Default")
      (node (ref "U35") (pin "9") (pinfunction "DP2_9") (pintype "unspecified"))
      (node (ref "USB4") (pin "7") (pinfunction "D+_7") (pintype "input"))
    )
    (net (code "25") (name "DP3") (class "Default")
      (node (ref "U35") (pin "7") (pinfunction "DP3_7") (pintype "unspecified"))
      (node (ref "USB3") (pin "3") (pinfunction "D+_3") (pintype "input"))
    )
    (net (code "26") (name "DP4") (class "Default")
      (node (ref "U35") (pin "5") (pinfunction "DP4_5") (pintype "unspecified"))
      (node (ref "USB3") (pin "7") (pinfunction "D+_7") (pintype "input"))
    )
    (net (code "27") (name "DPU") (class "Default")
      (node (ref "SW21") (pin "6") (pinfunction "6_6") (pintype "input"))
      (node (ref "U35") (pin "16") (pinfunction "DPU_16") (pintype "unspecified"))
    )
    (net (code "28") (name "DVDD") (class "Default")
      (node (ref "C100") (pin "2") (pinfunction "2_2") (pintype "input"))
      (node (ref "C101") (pin "2") (pinfunction "2_2") (pintype "input"))
      (node (ref "C115") (pin "2") (pinfunction "2_2") (pintype "input"))
      (node (ref "C116") (pin "2") (pinfunction "2_2") (pintype "input"))
      (node (ref "U28") (pin "10") (pinfunction "DVDD_10") (pintype "unspecified"))
      (node (ref "U28") (pin "32") (pinfunction "DVDD_32") (pintype "unspecified"))
      (node (ref "U28") (pin "51") (pinfunction "DVDD_51") (pintype "unspecified"))
      (node (ref "U37") (pin "5") (pinfunction "OUT_5") (pintype "unspecified"))
    )
    (net (code "29") (name "GND") (class "Default")
      (node (ref "BT6") (pin "2") (pinfunction "2_2") (pintype "input"))
      (node (ref "C100") (pin "1") (pinfunction "1_1") (pintype "input"))
      (node (ref "C101") (pin "1") (pinfunction "1_1") (pintype "input"))
      (node (ref "C102") (pin "1") (pinfunction "1_1") (pintype "input"))
      (node (ref "C103") (pin "1") (pinfunction "1_1") (pintype "input"))
      (node (ref "C104") (pin "1") (pinfunction "1_1") (pintype "input"))
      (node (ref "C105") (pin "1") (pinfunction "1_1") (pintype "input"))
      (node (ref "C106") (pin "1") (pinfunction "1_1") (pintype "input"))
      (node (ref "C107") (pin "1") (pinfunction "1_1") (pintype "input"))
      (node (ref "C108") (pin "1") (pinfunction "1_1") (pintype "input"))
      (node (ref "C109") (pin "1") (pinfunction "1_1") (pintype "input"))
      (node (ref "C110") (pin "1") (pinfunction "1_1") (pintype "input"))
      (node (ref "C111") (pin "1") (pinfunction "1_1") (pintype "input"))
      (node (ref "C112") (pin "1") (pinfunction "1_1") (pintype "input"))
      (node (ref "C113") (pin "1") (pinfunction "1_1") (pintype "input"))
      (node (ref "C114") (pin "1") (pinfunction "1_1") (pintype "input"))
      (node (ref "C115") (pin "1") (pinfunction "1_1") (pintype "input"))
      (node (ref "C116") (pin "1") (pinfunction "1_1") (pintype "input"))
      (node (ref "C118") (pin "1") (pinfunction "1_1") (pintype "input"))
      (node (ref "C119") (pin "2") (pinfunction "2_2") (pintype "unspecified"))
      (node (ref "C120") (pin "1") (pinfunction "1_1") (pintype "input"))
      (node (ref "C121") (pin "2") (pinfunction "2_2") (pintype "input"))
      (node (ref "C122") (pin "2") (pinfunction "2_2") (pintype "input"))
      (node (ref "C123") (pin "2") (pinfunction "2_2") (pintype "input"))
      (node (ref "C124") (pin "1") (pinfunction "1_1") (pintype "input"))
      (node (ref "C126") (pin "1") (pinfunction "1_1") (pintype "unspecified"))
      (node (ref "C22") (pin "1") (pinfunction "1_1") (pintype "input"))
      (node (ref "C25") (pin "1") (pinfunction "1_1") (pintype "input"))
      (node (ref "C26") (pin "1") (pinfunction "1_1") (pintype "input"))
      (node (ref "C27") (pin "1") (pinfunction "1_1") (pintype "input"))
      (node (ref "C34") (pin "2") (pinfunction "2_2") (pintype "input"))
      (node (ref "C35") (pin "1") (pinfunction "1_1") (pintype "input"))
      (node (ref "C60") (pin "1") (pinfunction "1_1") (pintype "input"))
      (node (ref "C63") (pin "2") (pinfunction "2_2") (pintype "input"))
      (node (ref "C66") (pin "1") (pinfunction "1_1") (pintype "input"))
      (node (ref "C67") (pin "1") (pinfunction "1_1") (pintype "input"))
      (node (ref "C84") (pin "2") (pinfunction "2_2") (pintype "input"))
      (node (ref "C85") (pin "2") (pinfunction "2_2") (pintype "input"))
      (node (ref "C86") (pin "1") (pinfunction "1_1") (pintype "input"))
      (node (ref "C88") (pin "1") (pinfunction "1_1") (pintype "input"))
      (node (ref "C89") (pin "1") (pinfunction "1_1") (pintype "input"))
      (node (ref "C97") (pin "2") (pinfunction "2_2") (pintype "unspecified"))
      (node (ref "C98") (pin "2") (pinfunction "2_2") (pintype "unspecified"))
      (node (ref "CARD2") (pin "10") (pinfunction "10_10") (pintype "input"))
      (node (ref "CARD2") (pin "11") (pinfunction "11_11") (pintype "input"))
      (node (ref "CARD2") (pin "12") (pinfunction "12_12") (pintype "input"))
      (node (ref "CARD2") (pin "13") (pinfunction "13_13") (pintype "input"))
      (node (ref "CARD2") (pin "6") (pinfunction "VSS_6") (pintype "input"))
      (node (ref "CN8") (pin "0") (pinfunction "0_0") (pintype "unspecified"))
      (node (ref "CN8") (pin "1") (pinfunction "1_1") (pintype "unspecified"))
      (node (ref "H2") (pin "3") (pinfunction "3_3") (pintype "unspecified"))
      (node (ref "H4") (pin "1") (pinfunction "1_1") (pintype "unspecified"))
      (node (ref "H4") (pin "2") (pinfunction "2_2") (pintype "unspecified"))
      (node (ref "H4") (pin "29") (pinfunction "29_29") (pintype "unspecified"))
      (node (ref "HDMI1") (pin "11") (pinfunction "TMDS_Clock_Shield_11") (pintype "input"))
      (node (ref "HDMI1") (pin "17") (pinfunction "DDC/CEC_Ground_17") (pintype "input"))
      (node (ref "HDMI1") (pin "2") (pinfunction "TMDS_Data2_Shield_2") (pintype "input"))
      (node (ref "HDMI1") (pin "20") (pinfunction "EH_20") (pintype "input"))
      (node (ref "HDMI1") (pin "21") (pinfunction "EH_21") (pintype "input"))
      (node (ref "HDMI1") (pin "22") (pinfunction "EH_22") (pintype "input"))
      (node (ref "HDMI1") (pin "23") (pinfunction "EH_23") (pintype "input"))
      (node (ref "HDMI1") (pin "5") (pinfunction "TMDS_Data1_Shield_5") (pintype "input"))
      (node (ref "HDMI1") (pin "8") (pinfunction "TMDS_Data0_Shield_8") (pintype "input"))
      (node (ref "L31") (pin "1") (pinfunction "1_1") (pintype "input"))
      (node (ref "LED1") (pin "1") (pinfunction "-_1") (pintype "input"))
      (node (ref "R101") (pin "1") (pinfunction "1_1") (pintype "input"))
      (node (ref "R31") (pin "1") (pinfunction "1_1") (pintype "input"))
      (node (ref "R32") (pin "1") (pinfunction "1_1") (pintype "input"))
      (node (ref "R33") (pin "1") (pinfunction "1_1") (pintype "input"))
      (node (ref "SW13") (pin "1") (pinfunction "1_1") (pintype "input"))
      (node (ref "SW13") (pin "3") (pinfunction "3_3") (pintype "input"))
      (node (ref "SW15") (pin "1") (pinfunction "1_1") (pintype "input"))
      (node (ref "SW15") (pin "3") (pinfunction "3_3") (pintype "input"))
      (node (ref "SW15") (pin "4") (pinfunction "4_4") (pintype "input"))
      (node (ref "SW22") (pin "2") (pinfunction "2_2") (pintype "unspecified"))
      (node (ref "U19") (pin "5") (pinfunction "GND_5") (pintype "unspecified"))
      (node (ref "U21") (pin "1") (pinfunction "GND_1") (pintype "input"))
      (node (ref "U24") (pin "1") (pinfunction "GND_1") (pintype "unspecified"))
      (node (ref "U27") (pin "10") (pinfunction "DEMP_10") (pintype "input"))
      (node (ref "U27") (pin "11") (pinfunction "FLT_11") (pintype "input"))
      (node (ref "U27") (pin "12") (pinfunction "SCK_12") (pintype "input"))
      (node (ref "U27") (pin "16") (pinfunction "FMT_16") (pintype "input"))
      (node (ref "U27") (pin "19") (pinfunction "DGND_19") (pintype "input"))
      (node (ref "U28") (pin "62") (pinfunction "VREG_PGND_62") (pintype "unspecified"))
      (node (ref "U28") (pin "65") (pinfunction "VREG_FB_65") (pintype "unspecified"))
      (node (ref "U28") (pin "81") (pinfunction "GND_81") (pintype "unspecified"))
      (node (ref "U33") (pin "4") (pinfunction "VSS_4") (pintype "unspecified"))
      (node (ref "U35") (pin "1") (pinfunction "GND_1") (pintype "unspecified"))
      (node (ref "U35") (pin "12") (pinfunction "GND_12") (pintype "unspecified"))
      (node (ref "U35") (pin "28") (pinfunction "GND_28") (pintype "unspecified"))
      (node (ref "U36") (pin "1") (pinfunction "Ground_1") (pintype "unspecified"))
      (node (ref "U36") (pin "11") (pinfunction "Ground_11") (pintype "unspecified"))
      (node (ref "U36") (pin "15") (pinfunction "Ground_15") (pintype "unspecified"))
      (node (ref "U36") (pin "21") (pinfunction "Ground_21") (pintype "unspecified"))
      (node (ref "U36") (pin "4") (pinfunction "Ground_4") (pintype "unspecified"))
      (node (ref "U36") (pin "7") (pinfunction "Ground_7") (pintype "unspecified"))
      (node (ref "U37") (pin "2") (pinfunction "GND_2") (pintype "unspecified"))
      (node (ref "U38") (pin "5") (pinfunction "GND_5") (pintype "unspecified"))
      (node (ref "U38") (pin "7") (pinfunction "EXP_7") (pintype "unspecified"))
      (node (ref "U6") (pin "4") (pinfunction "GND_4") (pintype "input"))
      (node (ref "U7") (pin "1") (pinfunction "GND_1") (pintype "input"))
      (node (ref "USB2") (pin "A1") (pinfunction "GND_A1") (pintype "input"))
      (node (ref "USB2") (pin "A12") (pinfunction "GND_A12") (pintype "input"))
      (node (ref "USB2") (pin "B1") (pinfunction "GND_B1") (pintype "input"))
      (node (ref "USB2") (pin "B12") (pinfunction "GND_B12") (pintype "input"))
      (node (ref "USB3") (pin "10") (pinfunction "SHELL_10") (pintype "input"))
      (node (ref "USB3") (pin "11") (pinfunction "SHELL_11") (pintype "input"))
      (node (ref "USB3") (pin "12") (pinfunction "SHELL_12") (pintype "input"))
      (node (ref "USB3") (pin "4") (pinfunction "GND_4") (pintype "input"))
      (node (ref "USB3") (pin "8") (pinfunction "GND_8") (pintype "input"))
      (node (ref "USB3") (pin "9") (pinfunction "SHELL_9") (pintype "input"))
      (node (ref "USB4") (pin "10") (pinfunction "SHELL_10") (pintype "input"))
      (node (ref "USB4") (pin "11") (pinfunction "SHELL_11") (pintype "input"))
      (node (ref "USB4") (pin "12") (pinfunction "SHELL_12") (pintype "input"))
      (node (ref "USB4") (pin "4") (pinfunction "GND_4") (pintype "input"))
      (node (ref "USB4") (pin "8") (pinfunction "GND_8") (pintype "input"))
      (node (ref "USB4") (pin "9") (pinfunction "SHELL_9") (pintype "input"))
      (node (ref "USB5") (pin "5") (pinfunction "GND_5") (pintype "unspecified"))
      (node (ref "USB5") (pin "6") (pinfunction "SH1_6") (pintype "unspecified"))
      (node (ref "USB5") (pin "7") (pinfunction "SH2_7") (pintype "unspecified"))
      (node (ref "USB5") (pin "8") (pinfunction "SH3_8") (pintype "unspecified"))
      (node (ref "USB5") (pin "9") (pinfunction "SH4_9") (pintype "unspecified"))
      (node (ref "X1") (pin "2") (pinfunction "GND_2") (pintype "unspecified"))
      (node (ref "X1") (pin "4") (pinfunction "GND_4") (pintype "unspecified"))
      (node (ref "X4") (pin "2") (pinfunction "GND_2") (pintype "unspecified"))
    )
    (net (code "30") (name "GPIO0") (class "Default")
      (node (ref "H4") (pin "5") (pinfunction "5_5") (pintype "unspecified"))
      (node (ref "U28") (pin "77") (pinfunction "GPIO0_77") (pintype "unspecified"))
    )
    (net (code "31") (name "GPIO1") (class "Default")
      (node (ref "H4") (pin "6") (pinfunction "6_6") (pintype "unspecified"))
      (node (ref "U28") (pin "78") (pinfunction "GPIO1_78") (pintype "unspecified"))
    )
    (net (code "32") (name "GPIO2") (class "Default")
      (node (ref "H4") (pin "7") (pinfunction "7_7") (pintype "unspecified"))
      (node (ref "U28") (pin "79") (pinfunction "GPIO2_79") (pintype "unspecified"))
    )
    (net (code "33") (name "GPIO3") (class "Default")
      (node (ref "H4") (pin "8") (pinfunction "8_8") (pintype "unspecified"))
      (node (ref "U28") (pin "80") (pinfunction "GPIO3_80") (pintype "unspecified"))
    )
    (net (code "34") (name "GPIO4") (class "Default")
      (node (ref "H4") (pin "9") (pinfunction "9_9") (pintype "unspecified"))
      (node (ref "U28") (pin "1") (pinfunction "GPIO4_1") (pintype "unspecified"))
    )
    (net (code "35") (name "GPIO5") (class "Default")
      (node (ref "H4") (pin "10") (pinfunction "10_10") (pintype "unspecified"))
      (node (ref "U28") (pin "2") (pinfunction "GPIO5_2") (pintype "unspecified"))
    )
    (net (code "36") (name "GPIO6") (class "Default")
      (node (ref "H4") (pin "11") (pinfunction "11_11") (pintype "unspecified"))
      (node (ref "U28") (pin "3") (pinfunction "GPIO6_3") (pintype "unspecified"))
    )
    (net (code "37") (name "GPIO7") (class "Default")
      (node (ref "H4") (pin "12") (pinfunction "12_12") (pintype "unspecified"))
      (node (ref "U28") (pin "4") (pinfunction "GPIO7_4") (pintype "unspecified"))
    )
    (net (code "38") (name "GPIO8") (class "Default")
      (node (ref "U28") (pin "6") (pinfunction "GPIO8_6") (pintype "unspecified"))
      (node (ref "U7") (pin "3") (pinfunction "RXD_3") (pintype "input"))
    )
    (net (code "39") (name "GPIO9") (class "Default")
      (node (ref "U28") (pin "7") (pinfunction "GPIO9_7") (pintype "unspecified"))
      (node (ref "U7") (pin "2") (pinfunction "TXD_2") (pintype "input"))
    )
    (net (code "40") (name "GPIO10") (class "Default")
      (node (ref "U27") (pin "13") (pinfunction "BCK_13") (pintype "input"))
      (node (ref "U28") (pin "8") (pinfunction "GPIO10_8") (pintype "unspecified"))
    )
    (net (code "41") (name "GPIO11") (class "Default")
      (node (ref "U27") (pin "15") (pinfunction "LRCK_15") (pintype "input"))
      (node (ref "U28") (pin "9") (pinfunction "GPIO11_9") (pintype "unspecified"))
    )
    (net (code "42") (name "GPIO12") (class "Default")
      (node (ref "R68") (pin "1") (pinfunction "1_1") (pintype "input"))
      (node (ref "U28") (pin "11") (pinfunction "GPIO12_11") (pintype "unspecified"))
    )
    (net (code "43") (name "GPIO13") (class "Default")
      (node (ref "R67") (pin "1") (pinfunction "1_1") (pintype "input"))
      (node (ref "U28") (pin "12") (pinfunction "GPIO13_12") (pintype "unspecified"))
    )
    (net (code "44") (name "GPIO14") (class "Default")
      (node (ref "R66") (pin "1") (pinfunction "1_1") (pintype "input"))
      (node (ref "U28") (pin "13") (pinfunction "GPIO14_13") (pintype "unspecified"))
    )
    (net (code "45") (name "GPIO15") (class "Default")
      (node (ref "R65") (pin "1") (pinfunction "1_1") (pintype "input"))
      (node (ref "U28") (pin "14") (pinfunction "GPIO15_14") (pintype "unspecified"))
    )
    (net (code "46") (name "GPIO16") (class "Default")
      (node (ref "R64") (pin "1") (pinfunction "1_1") (pintype "input"))
      (node (ref "U28") (pin "16") (pinfunction "GPIO16_16") (pintype "unspecified"))
    )
    (net (code "47") (name "GPIO17") (class "Default")
      (node (ref "R63") (pin "1") (pinfunction "1_1") (pintype "input"))
      (node (ref "U28") (pin "17") (pinfunction "GPIO17_17") (pintype "unspecified"))
    )
    (net (code "48") (name "GPIO18") (class "Default")
      (node (ref "R62") (pin "1") (pinfunction "1_1") (pintype "input"))
      (node (ref "U28") (pin "18") (pinfunction "GPIO18_18") (pintype "unspecified"))
    )
    (net (code "49") (name "GPIO19") (class "Default")
      (node (ref "R61") (pin "1") (pinfunction "1_1") (pintype "input"))
      (node (ref "U28") (pin "19") (pinfunction "GPIO19_19") (pintype "unspecified"))
    )
    (net (code "50") (name "GPIO20") (class "Default")
      (node (ref "CN8") (pin "3") (pinfunction "3_3") (pintype "unspecified"))
      (node (ref "H4") (pin "28") (pinfunction "28_28") (pintype "unspecified"))
      (node (ref "R52") (pin "1") (pinfunction "1_1") (pintype "input"))
      (node (ref "U19") (pin "7") (pinfunction "SDA_7") (pintype "bidirectional"))
      (node (ref "U28") (pin "20") (pinfunction "GPIO20_20") (pintype "unspecified"))
    )
    (net (code "51") (name "GPIO21") (class "Default")
      (node (ref "CN8") (pin "4") (pinfunction "4_4") (pintype "unspecified"))
      (node (ref "H4") (pin "30") (pinfunction "30_30") (pintype "unspecified"))
      (node (ref "R53") (pin "1") (pinfunction "1_1") (pintype "input"))
      (node (ref "U19") (pin "8") (pinfunction "SCL_8") (pintype "unspecified"))
      (node (ref "U28") (pin "21") (pinfunction "GPIO21_21") (pintype "unspecified"))
    )
    (net (code "52") (name "GPIO22") (class "Default")
      (node (ref "U27") (pin "14") (pinfunction "DIN_14") (pintype "input"))
      (node (ref "U28") (pin "22") (pinfunction "GPIO22_22") (pintype "unspecified"))
    )
    (net (code "53") (name "GPIO23") (class "Default")
      (node (ref "U28") (pin "23") (pinfunction "GPIO23_23") (pintype "unspecified"))
      (node (ref "U36") (pin "12") (pinfunction "Wi-Fi_on_12") (pintype "unspecified"))
      (node (ref "U36") (pin "13") (pinfunction "Bluetooth_on_13") (pintype "unspecified"))
    )
    (net (code "54") (name "GPIO24") (class "Default")
      (node (ref "R90") (pin "1") (pinfunction "1_1") (pintype "input"))
      (node (ref "R96") (pin "1") (pinfunction "1_1") (pintype "input"))
      (node (ref "U28") (pin "25") (pinfunction "GPIO24_25") (pintype "unspecified"))
      (node (ref "U36") (pin "5") (pinfunction "gSPI_Data_In_5") (pintype "unspecified"))
    )
    (net (code "55") (name "GPIO25") (class "Default")
      (node (ref "H5") (pin "1") (pinfunction "1_1") (pintype "unspecified"))
      (node (ref "U28") (pin "26") (pinfunction "GPIO25_26") (pintype "unspecified"))
      (node (ref "U36") (pin "9") (pinfunction "gSPICS_9") (pintype "unspecified"))
    )
    (net (code "56") (name "GPIO26") (class "Default")
      (node (ref "H4") (pin "14") (pinfunction "14_14") (pintype "unspecified"))
      (node (ref "U28") (pin "27") (pinfunction "GPIO26_27") (pintype "unspecified"))
    )
    (net (code "57") (name "GPIO27") (class "Default")
      (node (ref "R95") (pin "1") (pinfunction "1_1") (pintype "input"))
      (node (ref "U19") (pin "1") (pinfunction "32kHz_1") (pintype "unspecified"))
      (node (ref "U28") (pin "28") (pinfunction "GPIO27_28") (pintype "unspecified"))
    )
    (net (code "58") (name "GPIO28") (class "Default")
      (node (ref "CARD2") (pin "7") (pinfunction "DAT0_7") (pintype "input"))
      (node (ref "U28") (pin "36") (pinfunction "GPIO28_36") (pintype "unspecified"))
    )
    (net (code "59") (name "GPIO29") (class "Default")
      (node (ref "U28") (pin "37") (pinfunction "GPIO29_37") (pintype "unspecified"))
      (node (ref "U36") (pin "3") (pinfunction "gSPI_SCLK_3") (pintype "unspecified"))
    )
    (net (code "60") (name "GPIO30") (class "Default")
      (node (ref "CARD2") (pin "5") (pinfunction "CLX_5") (pintype "input"))
      (node (ref "U28") (pin "38") (pinfunction "GPIO30_38") (pintype "unspecified"))
    )
    (net (code "61") (name "GPIO31") (class "Default")
      (node (ref "CARD2") (pin "3") (pinfunction "CMD_3") (pintype "input"))
      (node (ref "U28") (pin "39") (pinfunction "GPIO31_39") (pintype "unspecified"))
    )
    (net (code "62") (name "GPIO32") (class "Default")
      (node (ref "R94") (pin "1") (pinfunction "1_1") (pintype "input"))
      (node (ref "U19") (pin "3") (pinfunction "INT#/SQW_3") (pintype "bidirectional"))
      (node (ref "U28") (pin "40") (pinfunction "GPIO32_40") (pintype "unspecified"))
    )
    (net (code "63") (name "GPIO33") (class "Default")
      (node (ref "CARD2") (pin "2") (pinfunction "CD/DAT3_2") (pintype "input"))
      (node (ref "U28") (pin "42") (pinfunction "GPIO33_42") (pintype "unspecified"))
    )
    (net (code "64") (name "GPIO34") (class "Default")
      (node (ref "H4") (pin "13") (pinfunction "13_13") (pintype "unspecified"))
      (node (ref "U28") (pin "43") (pinfunction "GPIO34_43") (pintype "unspecified"))
    )
    (net (code "65") (name "GPIO35") (class "Default")
      (node (ref "H4") (pin "16") (pinfunction "16_16") (pintype "unspecified"))
      (node (ref "U28") (pin "44") (pinfunction "GPIO35_44") (pintype "unspecified"))
    )
    (net (code "66") (name "GPIO36") (class "Default")
      (node (ref "H4") (pin "15") (pinfunction "15_15") (pintype "unspecified"))
      (node (ref "U28") (pin "45") (pinfunction "GPIO36_45") (pintype "unspecified"))
    )
    (net (code "67") (name "GPIO37") (class "Default")
      (node (ref "H4") (pin "18") (pinfunction "18_18") (pintype "unspecified"))
      (node (ref "U28") (pin "46") (pinfunction "GPIO37_46") (pintype "unspecified"))
    )
    (net (code "68") (name "GPIO38") (class "Default")
      (node (ref "H4") (pin "17") (pinfunction "17_17") (pintype "unspecified"))
      (node (ref "U28") (pin "47") (pinfunction "GPIO38_47") (pintype "unspecified"))
    )
    (net (code "69") (name "GPIO39") (class "Default")
      (node (ref "H4") (pin "20") (pinfunction "20_20") (pintype "unspecified"))
      (node (ref "U28") (pin "48") (pinfunction "GPIO39_48") (pintype "unspecified"))
    )
    (net (code "70") (name "GPIO40") (class "Default")
      (node (ref "H4") (pin "19") (pinfunction "19_19") (pintype "unspecified"))
      (node (ref "U28") (pin "49") (pinfunction "GPIO40_ADC0_49") (pintype "unspecified"))
    )
    (net (code "71") (name "GPIO41") (class "Default")
      (node (ref "H4") (pin "22") (pinfunction "22_22") (pintype "unspecified"))
      (node (ref "U28") (pin "52") (pinfunction "GPIO41_ADC1_52") (pintype "unspecified"))
    )
    (net (code "72") (name "GPIO42") (class "Default")
      (node (ref "H4") (pin "21") (pinfunction "21_21") (pintype "unspecified"))
      (node (ref "U28") (pin "53") (pinfunction "GPIO42_ADC2_53") (pintype "unspecified"))
    )
    (net (code "73") (name "GPIO43") (class "Default")
      (node (ref "H4") (pin "24") (pinfunction "24_24") (pintype "unspecified"))
      (node (ref "U28") (pin "54") (pinfunction "GPIO43_ADC3_54") (pintype "unspecified"))
    )
    (net (code "74") (name "GPIO44") (class "Default")
      (node (ref "H4") (pin "23") (pinfunction "23_23") (pintype "unspecified"))
      (node (ref "U28") (pin "55") (pinfunction "GPIO44_ADC4_55") (pintype "unspecified"))
    )
    (net (code "75") (name "GPIO45") (class "Default")
      (node (ref "H4") (pin "26") (pinfunction "26_26") (pintype "unspecified"))
      (node (ref "U28") (pin "56") (pinfunction "GPIO45_ADC5_56") (pintype "unspecified"))
    )
    (net (code "76") (name "GPIO46") (class "Default")
      (node (ref "H4") (pin "25") (pinfunction "25_25") (pintype "unspecified"))
      (node (ref "U28") (pin "57") (pinfunction "GPIO46_ADC6_57") (pintype "unspecified"))
    )
    (net (code "77") (name "HEARTBEAT") (class "Default")
      (node (ref "H5") (pin "2") (pinfunction "2_2") (pintype "unspecified"))
      (node (ref "R3") (pin "1") (pinfunction "1_1") (pintype "input"))
    )
    (net (code "78") (name "LED1") (class "Default")
      (node (ref "PORT3") (pin "1") (pinfunction "A_1") (pintype "unspecified"))
      (node (ref "PORT4") (pin "2") (pinfunction "K_2") (pintype "unspecified"))
      (node (ref "R58") (pin "2") (pinfunction "2_2") (pintype "input"))
    )
    (net (code "79") (name "LED2") (class "Default")
      (node (ref "PORT1") (pin "1") (pinfunction "A_1") (pintype "unspecified"))
      (node (ref "PORT2") (pin "2") (pinfunction "K_2") (pintype "unspecified"))
      (node (ref "R57") (pin "2") (pinfunction "2_2") (pintype "input"))
    )
    (net (code "80") (name "LED4") (class "Default")
      (node (ref "PORT1") (pin "2") (pinfunction "K_2") (pintype "unspecified"))
      (node (ref "PORT2") (pin "1") (pinfunction "A_1") (pintype "unspecified"))
      (node (ref "PORT3") (pin "2") (pinfunction "K_2") (pintype "unspecified"))
      (node (ref "PORT4") (pin "1") (pinfunction "A_1") (pintype "unspecified"))
      (node (ref "R59") (pin "1") (pinfunction "1_1") (pintype "input"))
      (node (ref "U35") (pin "22") (pinfunction "LED4/SDA_22") (pintype "unspecified"))
    )
    (net (code "81") (name "Net-(ACTIVE-K)") (class "Default")
      (node (ref "ACTIVE") (pin "1") (pinfunction "K_1") (pintype "input"))
      (node (ref "R59") (pin "2") (pinfunction "2_2") (pintype "input"))
    )
    (net (code "82") (name "Net-(C95-Pad2)") (class "Default")
      (node (ref "C95") (pin "2") (pinfunction "2_2") (pintype "input"))
      (node (ref "CN5") (pin "3") (pinfunction "3_3") (pintype "input"))
      (node (ref "R70") (pin "1") (pinfunction "1_1") (pintype "input"))
    )
    (net (code "83") (name "Net-(C96-Pad2)") (class "Default")
      (node (ref "C96") (pin "2") (pinfunction "2_2") (pintype "input"))
      (node (ref "CN5") (pin "2") (pinfunction "2_2") (pintype "input"))
      (node (ref "R69") (pin "1") (pinfunction "1_1") (pintype "input"))
    )
    (net (code "84") (name "Net-(C118-Pad2)") (class "Default")
      (node (ref "C118") (pin "2") (pinfunction "2_2") (pintype "input"))
      (node (ref "L29") (pin "2") (pinfunction "2_2") (pintype "unspecified"))
      (node (ref "R79") (pin "1") (pinfunction "1_1") (pintype "input"))
    )
    (net (code "85") (name "Net-(CARD2-VDD)") (class "Default")
      (node (ref "C120") (pin "2") (pinfunction "2_2") (pintype "input"))
      (node (ref "C27") (pin "2") (pinfunction "2_2") (pintype "input"))
      (node (ref "CARD2") (pin "4") (pinfunction "VDD_4") (pintype "input"))
      (node (ref "R29") (pin "1") (pinfunction "1_1") (pintype "input"))
    )
    (net (code "86") (name "Net-(D1-K)") (class "Default")
      (node (ref "D1") (pin "1") (pinfunction "K_1") (pintype "unspecified"))
      (node (ref "HDMI1") (pin "18") (pinfunction "+5V_Power_18") (pintype "input"))
    )
    (net (code "87") (name "Net-(D2-A)") (class "Default")
      (node (ref "D2") (pin "2") (pinfunction "A_2") (pintype "unspecified"))
      (node (ref "USB5") (pin "1") (pinfunction "VBUS_1") (pintype "unspecified"))
    )
    (net (code "88") (name "Net-(HDMI1-TMDS_Clock+)") (class "Default")
      (node (ref "HDMI1") (pin "10") (pinfunction "TMDS_Clock+_10") (pintype "input"))
      (node (ref "R67") (pin "2") (pinfunction "2_2") (pintype "input"))
    )
    (net (code "89") (name "Net-(HDMI1-TMDS_Clock-)") (class "Default")
      (node (ref "HDMI1") (pin "12") (pinfunction "TMDS_Clock-_12") (pintype "input"))
      (node (ref "R68") (pin "2") (pinfunction "2_2") (pintype "input"))
    )
    (net (code "90") (name "Net-(HDMI1-TMDS_Data0+)") (class "Default")
      (node (ref "HDMI1") (pin "7") (pinfunction "TMDS_Data0+_7") (pintype "input"))
      (node (ref "R65") (pin "2") (pinfunction "2_2") (pintype "input"))
    )
    (net (code "91") (name "Net-(HDMI1-TMDS_Data1+)") (class "Default")
      (node (ref "HDMI1") (pin "4") (pinfunction "TMDS_Data1+_4") (pintype "input"))
      (node (ref "R63") (pin "2") (pinfunction "2_2") (pintype "input"))
    )
    (net (code "92") (name "Net-(HDMI1-TMDS_Data1-)") (class "Default")
      (node (ref "HDMI1") (pin "6") (pinfunction "TMDS_Data1-_6") (pintype "input"))
      (node (ref "R64") (pin "2") (pinfunction "2_2") (pintype "input"))
    )
    (net (code "93") (name "Net-(HDMI1-TMDS_Data2+)") (class "Default")
      (node (ref "HDMI1") (pin "1") (pinfunction "TMDS_Data2+_1") (pintype "input"))
      (node (ref "R61") (pin "2") (pinfunction "2_2") (pintype "input"))
    )
    (net (code "94") (name "Net-(HDMI1-TMDS_Data2-)") (class "Default")
      (node (ref "HDMI1") (pin "3") (pinfunction "TMDS_Data2-_3") (pintype "input"))
      (node (ref "R62") (pin "2") (pinfunction "2_2") (pintype "input"))
    )
    (net (code "95") (name "Net-(HDMI1-TMDS_Data_0-)") (class "Default")
      (node (ref "HDMI1") (pin "9") (pinfunction "TMDS_Data_0-_9") (pintype "input"))
      (node (ref "R66") (pin "2") (pinfunction "2_2") (pintype "input"))
    )
    (net (code "96") (name "Net-(LED1-+)") (class "Default")
      (node (ref "LED1") (pin "2") (pinfunction "+_2") (pintype "input"))
      (node (ref "R3") (pin "2") (pinfunction "2_2") (pintype "input"))
    )
    (net (code "97") (name "Net-(R4-Pad2)") (class "Default")
      (node (ref "R4") (pin "2") (pinfunction "2_2") (pintype "input"))
      (node (ref "SW22") (pin "1") (pinfunction "1_1") (pintype "unspecified"))
    )
    (net (code "98") (name "Net-(R33-Pad2)") (class "Default")
      (node (ref "R33") (pin "2") (pinfunction "2_2") (pintype "input"))
      (node (ref "USB2") (pin "1") (pinfunction "EP_1") (pintype "input"))
      (node (ref "USB2") (pin "2") (pinfunction "EP_2") (pintype "input"))
      (node (ref "USB2") (pin "3") (pinfunction "EP_3") (pintype "input"))
      (node (ref "USB2") (pin "4") (pinfunction "EP_4") (pintype "input"))
    )
    (net (code "99") (name "Net-(U24-RESET)") (class "Default")
      (node (ref "R60") (pin "2") (pinfunction "2_2") (pintype "input"))
      (node (ref "U24") (pin "2") (pinfunction "RESET_2") (pintype "unspecified"))
    )
    (net (code "100") (name "Net-(U27-CAPM)") (class "Default")
      (node (ref "C81") (pin "2") (pinfunction "2_2") (pintype "input"))
      (node (ref "U27") (pin "4") (pinfunction "CAPM_4") (pintype "input"))
    )
    (net (code "101") (name "Net-(U27-CAPP)") (class "Default")
      (node (ref "C81") (pin "1") (pinfunction "1_1") (pintype "input"))
      (node (ref "U27") (pin "2") (pinfunction "CAPP_2") (pintype "input"))
    )
    (net (code "102") (name "Net-(U27-LDOO)") (class "Default")
      (node (ref "C97") (pin "1") (pinfunction "1_1") (pintype "unspecified"))
      (node (ref "C98") (pin "1") (pinfunction "1_1") (pintype "unspecified"))
      (node (ref "U27") (pin "18") (pinfunction "LDOO_18") (pintype "input"))
    )
    (net (code "103") (name "Net-(U27-OUTL)") (class "Default")
      (node (ref "R70") (pin "2") (pinfunction "2_2") (pintype "input"))
      (node (ref "U27") (pin "6") (pinfunction "OUTL_6") (pintype "input"))
    )
    (net (code "104") (name "Net-(U27-OUTR)") (class "Default")
      (node (ref "R69") (pin "2") (pinfunction "2_2") (pintype "input"))
      (node (ref "U27") (pin "7") (pinfunction "OUTR_7") (pintype "input"))
    )
    (net (code "105") (name "Net-(U27-VNEG)") (class "Default")
      (node (ref "C93") (pin "1") (pinfunction "1_1") (pintype "input"))
      (node (ref "U27") (pin "5") (pinfunction "VNEG_5") (pintype "input"))
    )
    (net (code "106") (name "Net-(U28-XIN)") (class "Default")
      (node (ref "U28") (pin "30") (pinfunction "XIN_30") (pintype "unspecified"))
      (node (ref "X4") (pin "3") (pinfunction "OUT_3") (pintype "unspecified"))
    )
    (net (code "107") (name "Net-(U35-LED1{slash}PSELF)") (class "Default")
      (node (ref "R58") (pin "1") (pinfunction "1_1") (pintype "input"))
      (node (ref "U35") (pin "23") (pinfunction "LED1/PSELF_23") (pintype "unspecified"))
    )
    (net (code "108") (name "Net-(U35-LED2{slash}PGANG)") (class "Default")
      (node (ref "R57") (pin "1") (pinfunction "1_1") (pintype "input"))
      (node (ref "U35") (pin "24") (pinfunction "LED2/PGANG_24") (pintype "unspecified"))
    )
    (net (code "109") (name "Net-(U36-GPIO0)") (class "Default")
      (node (ref "H5") (pin "3") (pinfunction "3_3") (pintype "unspecified"))
      (node (ref "U36") (pin "8") (pinfunction "GPIO0_8") (pintype "unspecified"))
    )
    (net (code "110") (name "Net-(U36-gSPI_Data_out)") (class "Default")
      (node (ref "R90") (pin "2") (pinfunction "2_2") (pintype "input"))
      (node (ref "U36") (pin "6") (pinfunction "gSPI_Data_out_6") (pintype "unspecified"))
    )
    (net (code "111") (name "Net-(U36-nIRQ)") (class "Default")
      (node (ref "R96") (pin "2") (pinfunction "2_2") (pintype "input"))
      (node (ref "U36") (pin "10") (pinfunction "nIRQ_10") (pintype "unspecified"))
    )
    (net (code "112") (name "Net-(U38-ILIM)") (class "Default")
      (node (ref "R101") (pin "2") (pinfunction "2_2") (pintype "input"))
      (node (ref "U38") (pin "2") (pinfunction "ILIM_2") (pintype "unspecified"))
    )
    (net (code "113") (name "Net-(USB2-CC1)") (class "Default")
      (node (ref "R32") (pin "2") (pinfunction "2_2") (pintype "input"))
      (node (ref "USB2") (pin "A5") (pinfunction "CC1_A5") (pintype "input"))
    )
    (net (code "114") (name "Net-(USB2-CC2)") (class "Default")
      (node (ref "R31") (pin "2") (pinfunction "2_2") (pintype "input"))
      (node (ref "USB2") (pin "B5") (pinfunction "CC2_B5") (pintype "input"))
    )
    (net (code "115") (name "PSRAM_SS") (class "Default")
      (node (ref "R97") (pin "1") (pinfunction "1_1") (pintype "input"))
      (node (ref "U28") (pin "58") (pinfunction "GPIO47_ADC7_58") (pintype "unspecified"))
      (node (ref "U33") (pin "1") (pinfunction "CE#_1") (pintype "unspecified"))
    )
    (net (code "116") (name "QSPI_SCLK") (class "Default")
      (node (ref "U28") (pin "71") (pinfunction "QSPI_SCLK_71") (pintype "unspecified"))
      (node (ref "U33") (pin "6") (pinfunction "SCLK_6") (pintype "unspecified"))
      (node (ref "U6") (pin "6") (pinfunction "CLK_6") (pintype "input"))
    )
    (net (code "117") (name "QSPI_SD0") (class "Default")
      (node (ref "U28") (pin "72") (pinfunction "QSPI_SD0_72") (pintype "unspecified"))
      (node (ref "U33") (pin "5") (pinfunction "SI/SIO[0]_5") (pintype "unspecified"))
      (node (ref "U6") (pin "5") (pinfunction "DI_5") (pintype "input"))
    )
    (net (code "118") (name "QSPI_SD1") (class "Default")
      (node (ref "U28") (pin "74") (pinfunction "QSPI_SD1_74") (pintype "unspecified"))
      (node (ref "U33") (pin "2") (pinfunction "SO/SIO[1]_2") (pintype "unspecified"))
      (node (ref "U6") (pin "2") (pinfunction "DO_2") (pintype "input"))
    )
    (net (code "119") (name "QSPI_SD2") (class "Default")
      (node (ref "U28") (pin "73") (pinfunction "QSPI_SD2_73") (pintype "unspecified"))
      (node (ref "U33") (pin "3") (pinfunction "SIO[2]_3") (pintype "unspecified"))
      (node (ref "U6") (pin "3") (pinfunction "IO2_3") (pintype "input"))
    )
    (net (code "120") (name "QSPI_SD3") (class "Default")
      (node (ref "U28") (pin "70") (pinfunction "QSPI_SD3_70") (pintype "unspecified"))
      (node (ref "U33") (pin "7") (pinfunction "SIO[3]_7") (pintype "unspecified"))
      (node (ref "U6") (pin "7") (pinfunction "IO3_7") (pintype "input"))
    )
    (net (code "121") (name "QSPI_SS") (class "Default")
      (node (ref "R4") (pin "1") (pinfunction "1_1") (pintype "input"))
      (node (ref "R98") (pin "1") (pinfunction "1_1") (pintype "input"))
      (node (ref "U28") (pin "75") (pinfunction "QSPI_SS_75") (pintype "unspecified"))
      (node (ref "U6") (pin "1") (pinfunction "CS#_1") (pintype "input"))
    )
    (net (code "122") (name "RESET") (class "Default")
      (node (ref "R60") (pin "1") (pinfunction "1_1") (pintype "input"))
      (node (ref "SW15") (pin "2") (pinfunction "2_2") (pintype "input"))
      (node (ref "U28") (pin "35") (pinfunction "RUN_35") (pintype "unspecified"))
      (node (ref "U35") (pin "17") (pinfunction "RESET#/CDP_17") (pintype "unspecified"))
    )
    (net (code "123") (name "USB-DM") (class "Default")
      (node (ref "U7") (pin "6") (pinfunction "D-_6") (pintype "input"))
      (node (ref "USB2") (pin "A7") (pinfunction "DN1_A7") (pintype "input"))
      (node (ref "USB2") (pin "B7") (pinfunction "DN2_B7") (pintype "input"))
    )
    (net (code "124") (name "USB-DP") (class "Default")
      (node (ref "U7") (pin "5") (pinfunction "D+_5") (pintype "input"))
      (node (ref "USB2") (pin "A6") (pinfunction "DP1_A6") (pintype "input"))
      (node (ref "USB2") (pin "B6") (pinfunction "DP2_B6") (pintype "input"))
    )
    (net (code "125") (name "USB_HOST_DM") (class "Default")
      (node (ref "SW21") (pin "2") (pinfunction "2_2") (pintype "input"))
      (node (ref "U28") (pin "66") (pinfunction "USB_DM_66") (pintype "unspecified"))
    )
    (net (code "126") (name "USB_HOST_DP") (class "Default")
      (node (ref "SW21") (pin "5") (pinfunction "5_5") (pintype "input"))
      (node (ref "U28") (pin "67") (pinfunction "USB_DP_67") (pintype "unspecified"))
    )
    (net (code "127") (name "VCC") (class "Default")
      (node (ref "ACTIVE") (pin "2") (pinfunction "A_2") (pintype "input"))
      (node (ref "C102") (pin "2") (pinfunction "2_2") (pintype "input"))
      (node (ref "C104") (pin "2") (pinfunction "2_2") (pintype "input"))
      (node (ref "C105") (pin "2") (pinfunction "2_2") (pintype "input"))
      (node (ref "C106") (pin "2") (pinfunction "2_2") (pintype "input"))
      (node (ref "C107") (pin "2") (pinfunction "2_2") (pintype "input"))
      (node (ref "C108") (pin "2") (pinfunction "2_2") (pintype "input"))
      (node (ref "C109") (pin "2") (pinfunction "2_2") (pintype "input"))
      (node (ref "C110") (pin "2") (pinfunction "2_2") (pintype "input"))
      (node (ref "C111") (pin "2") (pinfunction "2_2") (pintype "input"))
      (node (ref "C112") (pin "2") (pinfunction "2_2") (pintype "input"))
      (node (ref "C113") (pin "2") (pinfunction "2_2") (pintype "input"))
      (node (ref "C114") (pin "2") (pinfunction "2_2") (pintype "input"))
      (node (ref "C126") (pin "2") (pinfunction "2_2") (pintype "unspecified"))
      (node (ref "C22") (pin "2") (pinfunction "2_2") (pintype "input"))
      (node (ref "C26") (pin "2") (pinfunction "2_2") (pintype "input"))
      (node (ref "C34") (pin "1") (pinfunction "1_1") (pintype "input"))
      (node (ref "C60") (pin "2") (pinfunction "2_2") (pintype "input"))
      (node (ref "C66") (pin "2") (pinfunction "2_2") (pintype "input"))
      (node (ref "C84") (pin "1") (pinfunction "1_1") (pintype "input"))
      (node (ref "C86") (pin "2") (pinfunction "2_2") (pintype "input"))
      (node (ref "C88") (pin "2") (pinfunction "2_2") (pintype "input"))
      (node (ref "C89") (pin "2") (pinfunction "2_2") (pintype "input"))
      (node (ref "CN8") (pin "2") (pinfunction "2_2") (pintype "unspecified"))
      (node (ref "FB1") (pin "2") (pinfunction "2_2") (pintype "unspecified"))
      (node (ref "H4") (pin "3") (pinfunction "3_3") (pintype "unspecified"))
      (node (ref "H4") (pin "4") (pinfunction "4_4") (pintype "unspecified"))
      (node (ref "L30") (pin "2") (pinfunction "2_2") (pintype "input"))
      (node (ref "R102") (pin "2") (pinfunction "2_2") (pintype "input"))
      (node (ref "R29") (pin "2") (pinfunction "2_2") (pintype "input"))
      (node (ref "R52") (pin "2") (pinfunction "2_2") (pintype "input"))
      (node (ref "R53") (pin "2") (pinfunction "2_2") (pintype "input"))
      (node (ref "R79") (pin "2") (pinfunction "2_2") (pintype "input"))
      (node (ref "R88") (pin "1") (pinfunction "1_1") (pintype "input"))
      (node (ref "R94") (pin "2") (pinfunction "2_2") (pintype "input"))
      (node (ref "R95") (pin "2") (pinfunction "2_2") (pintype "input"))
      (node (ref "R97") (pin "2") (pinfunction "2_2") (pintype "input"))
      (node (ref "R98") (pin "2") (pinfunction "2_2") (pintype "input"))
      (node (ref "U19") (pin "2") (pinfunction "VCC_2") (pintype "unspecified"))
      (node (ref "U19") (pin "4") (pinfunction "RST#_4") (pintype "bidirectional"))
      (node (ref "U21") (pin "2") (pinfunction "VOUT_2") (pintype "input"))
      (node (ref "U21") (pin "4") (pinfunction "VOUT_4") (pintype "input"))
      (node (ref "U24") (pin "3") (pinfunction "VDD_3") (pintype "unspecified"))
      (node (ref "U27") (pin "17") (pinfunction "XSMT_17") (pintype "input"))
      (node (ref "U27") (pin "20") (pinfunction "DVDD_20") (pintype "input"))
      (node (ref "U28") (pin "15") (pinfunction "IOVDD_15") (pintype "unspecified"))
      (node (ref "U28") (pin "24") (pinfunction "IOVDD_24") (pintype "unspecified"))
      (node (ref "U28") (pin "29") (pinfunction "IOVDD_29") (pintype "unspecified"))
      (node (ref "U28") (pin "41") (pinfunction "IOVDD_41") (pintype "unspecified"))
      (node (ref "U28") (pin "5") (pinfunction "IOVDD_5") (pintype "unspecified"))
      (node (ref "U28") (pin "50") (pinfunction "IOVDD_50") (pintype "unspecified"))
      (node (ref "U28") (pin "59") (pinfunction "ADC_AVDD_59") (pintype "unspecified"))
      (node (ref "U28") (pin "60") (pinfunction "IOVDD_60") (pintype "unspecified"))
      (node (ref "U28") (pin "68") (pinfunction "USB_OTP_VDD_68") (pintype "unspecified"))
      (node (ref "U28") (pin "69") (pinfunction "QSPI_IOVDD_69") (pintype "unspecified"))
      (node (ref "U28") (pin "76") (pinfunction "IOVDD_76") (pintype "unspecified"))
      (node (ref "U33") (pin "8") (pinfunction "VDD_8") (pintype "unspecified"))
      (node (ref "U35") (pin "13") (pinfunction "VDD33_13") (pintype "unspecified"))
      (node (ref "U35") (pin "20") (pinfunction "V5_20") (pintype "unspecified"))
      (node (ref "U35") (pin "21") (pinfunction "VDD33_21") (pintype "unspecified"))
      (node (ref "U37") (pin "1") (pinfunction "IN_1") (pintype "unspecified"))
      (node (ref "U37") (pin "3") (pinfunction "EN_3") (pintype "unspecified"))
      (node (ref "U6") (pin "8") (pinfunction "VCC_8") (pintype "input"))
      (node (ref "U7") (pin "16") (pinfunction "VCC_16") (pintype "input"))
      (node (ref "U7") (pin "4") (pinfunction "V3_4") (pintype "input"))
      (node (ref "X4") (pin "1") (pinfunction "TRI-STATE_1") (pintype "unspecified"))
      (node (ref "X4") (pin "4") (pinfunction "VDD_4") (pintype "unspecified"))
    )
    (net (code "128") (name "unconnected-(CARD2-DAT1-Pad8)") (class "Default")
      (node (ref "CARD2") (pin "8") (pinfunction "DAT1_8") (pintype "input+no_connect"))
    )
    (net (code "129") (name "unconnected-(CARD2-DAT2-Pad1)") (class "Default")
      (node (ref "CARD2") (pin "1") (pinfunction "DAT2_1") (pintype "input+no_connect"))
    )
    (net (code "130") (name "unconnected-(CARD2-PadCD)") (class "Default")
      (node (ref "CARD2") (pin "CD") (pinfunction "CD_CD") (pintype "input+no_connect"))
    )
    (net (code "131") (name "unconnected-(HDMI1-CEC-Pad13)") (class "Default")
      (node (ref "HDMI1") (pin "13") (pinfunction "CEC_13") (pintype "input+no_connect"))
    )
    (net (code "132") (name "unconnected-(HDMI1-Hot_Plug_Detect-Pad19)") (class "Default")
      (node (ref "HDMI1") (pin "19") (pinfunction "Hot_Plug_Detect_19") (pintype "input+no_connect"))
    )
    (net (code "133") (name "unconnected-(HDMI1-Reserved(N.C.)-Pad14)") (class "Default")
      (node (ref "HDMI1") (pin "14") (pinfunction "Reserved(N.C.)_14") (pintype "input+no_connect"))
    )
    (net (code "134") (name "unconnected-(HDMI1-SCL-Pad15)") (class "Default")
      (node (ref "HDMI1") (pin "15") (pinfunction "SCL_15") (pintype "input+no_connect"))
    )
    (net (code "135") (name "unconnected-(HDMI1-SDA-Pad16)") (class "Default")
      (node (ref "HDMI1") (pin "16") (pinfunction "SDA_16") (pintype "input+no_connect"))
    )
    (net (code "136") (name "unconnected-(U7-CTS#-Pad9)") (class "Default")
      (node (ref "U7") (pin "9") (pinfunction "CTS#_9") (pintype "input+no_connect"))
    )
    (net (code "137") (name "unconnected-(U7-DCD#-Pad12)") (class "Default")
      (node (ref "U7") (pin "12") (pinfunction "DCD#_12") (pintype "input+no_connect"))
    )
    (net (code "138") (name "unconnected-(U7-DSR#-Pad10)") (class "Default")
      (node (ref "U7") (pin "10") (pinfunction "DSR#_10") (pintype "input+no_connect"))
    )
    (net (code "139") (name "unconnected-(U7-DTR#-Pad13)") (class "Default")
      (node (ref "U7") (pin "13") (pinfunction "DTR#_13") (pintype "input+no_connect"))
    )
    (net (code "140") (name "unconnected-(U7-NC.-Pad7)") (class "Default")
      (node (ref "U7") (pin "7") (pinfunction "NC._7") (pintype "input+no_connect"))
    )
    (net (code "141") (name "unconnected-(U7-OUT#-Pad8)") (class "Default")
      (node (ref "U7") (pin "8") (pinfunction "OUT#_8") (pintype "input+no_connect"))
    )
    (net (code "142") (name "unconnected-(U7-R232-Pad15)") (class "Default")
      (node (ref "U7") (pin "15") (pinfunction "R232_15") (pintype "input+no_connect"))
    )
    (net (code "143") (name "unconnected-(U7-RI#-Pad11)") (class "Default")
      (node (ref "U7") (pin "11") (pinfunction "RI#_11") (pintype "input+no_connect"))
    )
    (net (code "144") (name "unconnected-(U7-RTS#-Pad14)") (class "Default")
      (node (ref "U7") (pin "14") (pinfunction "RTS#_14") (pintype "input+no_connect"))
    )
    (net (code "145") (name "unconnected-(U28-VREG_LX-Pad63)") (class "Default")
      (node (ref "U28") (pin "63") (pinfunction "VREG_LX_63") (pintype "unspecified+no_connect"))
    )
    (net (code "146") (name "unconnected-(U28-XOUT-Pad31)") (class "Default")
      (node (ref "U28") (pin "31") (pinfunction "XOUT_31") (pintype "unspecified+no_connect"))
    )
    (net (code "147") (name "unconnected-(U35-LED3{slash}SCL-Pad14)") (class "Default")
      (node (ref "U35") (pin "14") (pinfunction "LED3/SCL_14") (pintype "unspecified+no_connect"))
    )
    (net (code "148") (name "unconnected-(U35-NC-Pad18)") (class "Default")
      (node (ref "U35") (pin "18") (pinfunction "NC_18") (pintype "unspecified+no_connect"))
    )
    (net (code "149") (name "unconnected-(U35-NC-Pad27)") (class "Default")
      (node (ref "U35") (pin "27") (pinfunction "NC_27") (pintype "unspecified+no_connect"))
    )
    (net (code "150") (name "unconnected-(U35-PSELF-Pad19)") (class "Default")
      (node (ref "U35") (pin "19") (pinfunction "PSELF_19") (pintype "unspecified+no_connect"))
    )
    (net (code "151") (name "unconnected-(U36-GPIO1-Pad18)") (class "Default")
      (node (ref "U36") (pin "18") (pinfunction "GPIO1_18") (pintype "unspecified+no_connect"))
    )
    (net (code "152") (name "unconnected-(U36-GPIO2-Pad17)") (class "Default")
      (node (ref "U36") (pin "17") (pinfunction "GPIO2_17") (pintype "unspecified+no_connect"))
    )
    (net (code "153") (name "unconnected-(U36-nc-Pad2)") (class "Default")
      (node (ref "U36") (pin "2") (pinfunction "nc_2") (pintype "unspecified+no_connect"))
    )
    (net (code "154") (name "unconnected-(U36-nc-Pad19)") (class "Default")
      (node (ref "U36") (pin "19") (pinfunction "nc_19") (pintype "unspecified+no_connect"))
    )
    (net (code "155") (name "unconnected-(U36-nc-Pad20)") (class "Default")
      (node (ref "U36") (pin "20") (pinfunction "nc_20") (pintype "unspecified+no_connect"))
    )
    (net (code "156") (name "unconnected-(U37-NC-Pad4)") (class "Default")
      (node (ref "U37") (pin "4") (pinfunction "NC_4") (pintype "unspecified+no_connect"))
    )
    (net (code "157") (name "unconnected-(USB2-SUB1-PadA8)") (class "Default")
      (node (ref "USB2") (pin "A8") (pinfunction "SUB1_A8") (pintype "input+no_connect"))
    )
    (net (code "158") (name "unconnected-(USB2-SUB2-PadB8)") (class "Default")
      (node (ref "USB2") (pin "B8") (pinfunction "SUB2_B8") (pintype "input+no_connect"))
    )
    (net (code "159") (name "unconnected-(USB5-ID-Pad4)") (class "Default")
      (node (ref "USB5") (pin "4") (pinfunction "ID_4") (pintype "unspecified+no_connect"))
    )
  )
)
